# hot-wand.net
KiCad netlist of a schematic drawn in EAGLE
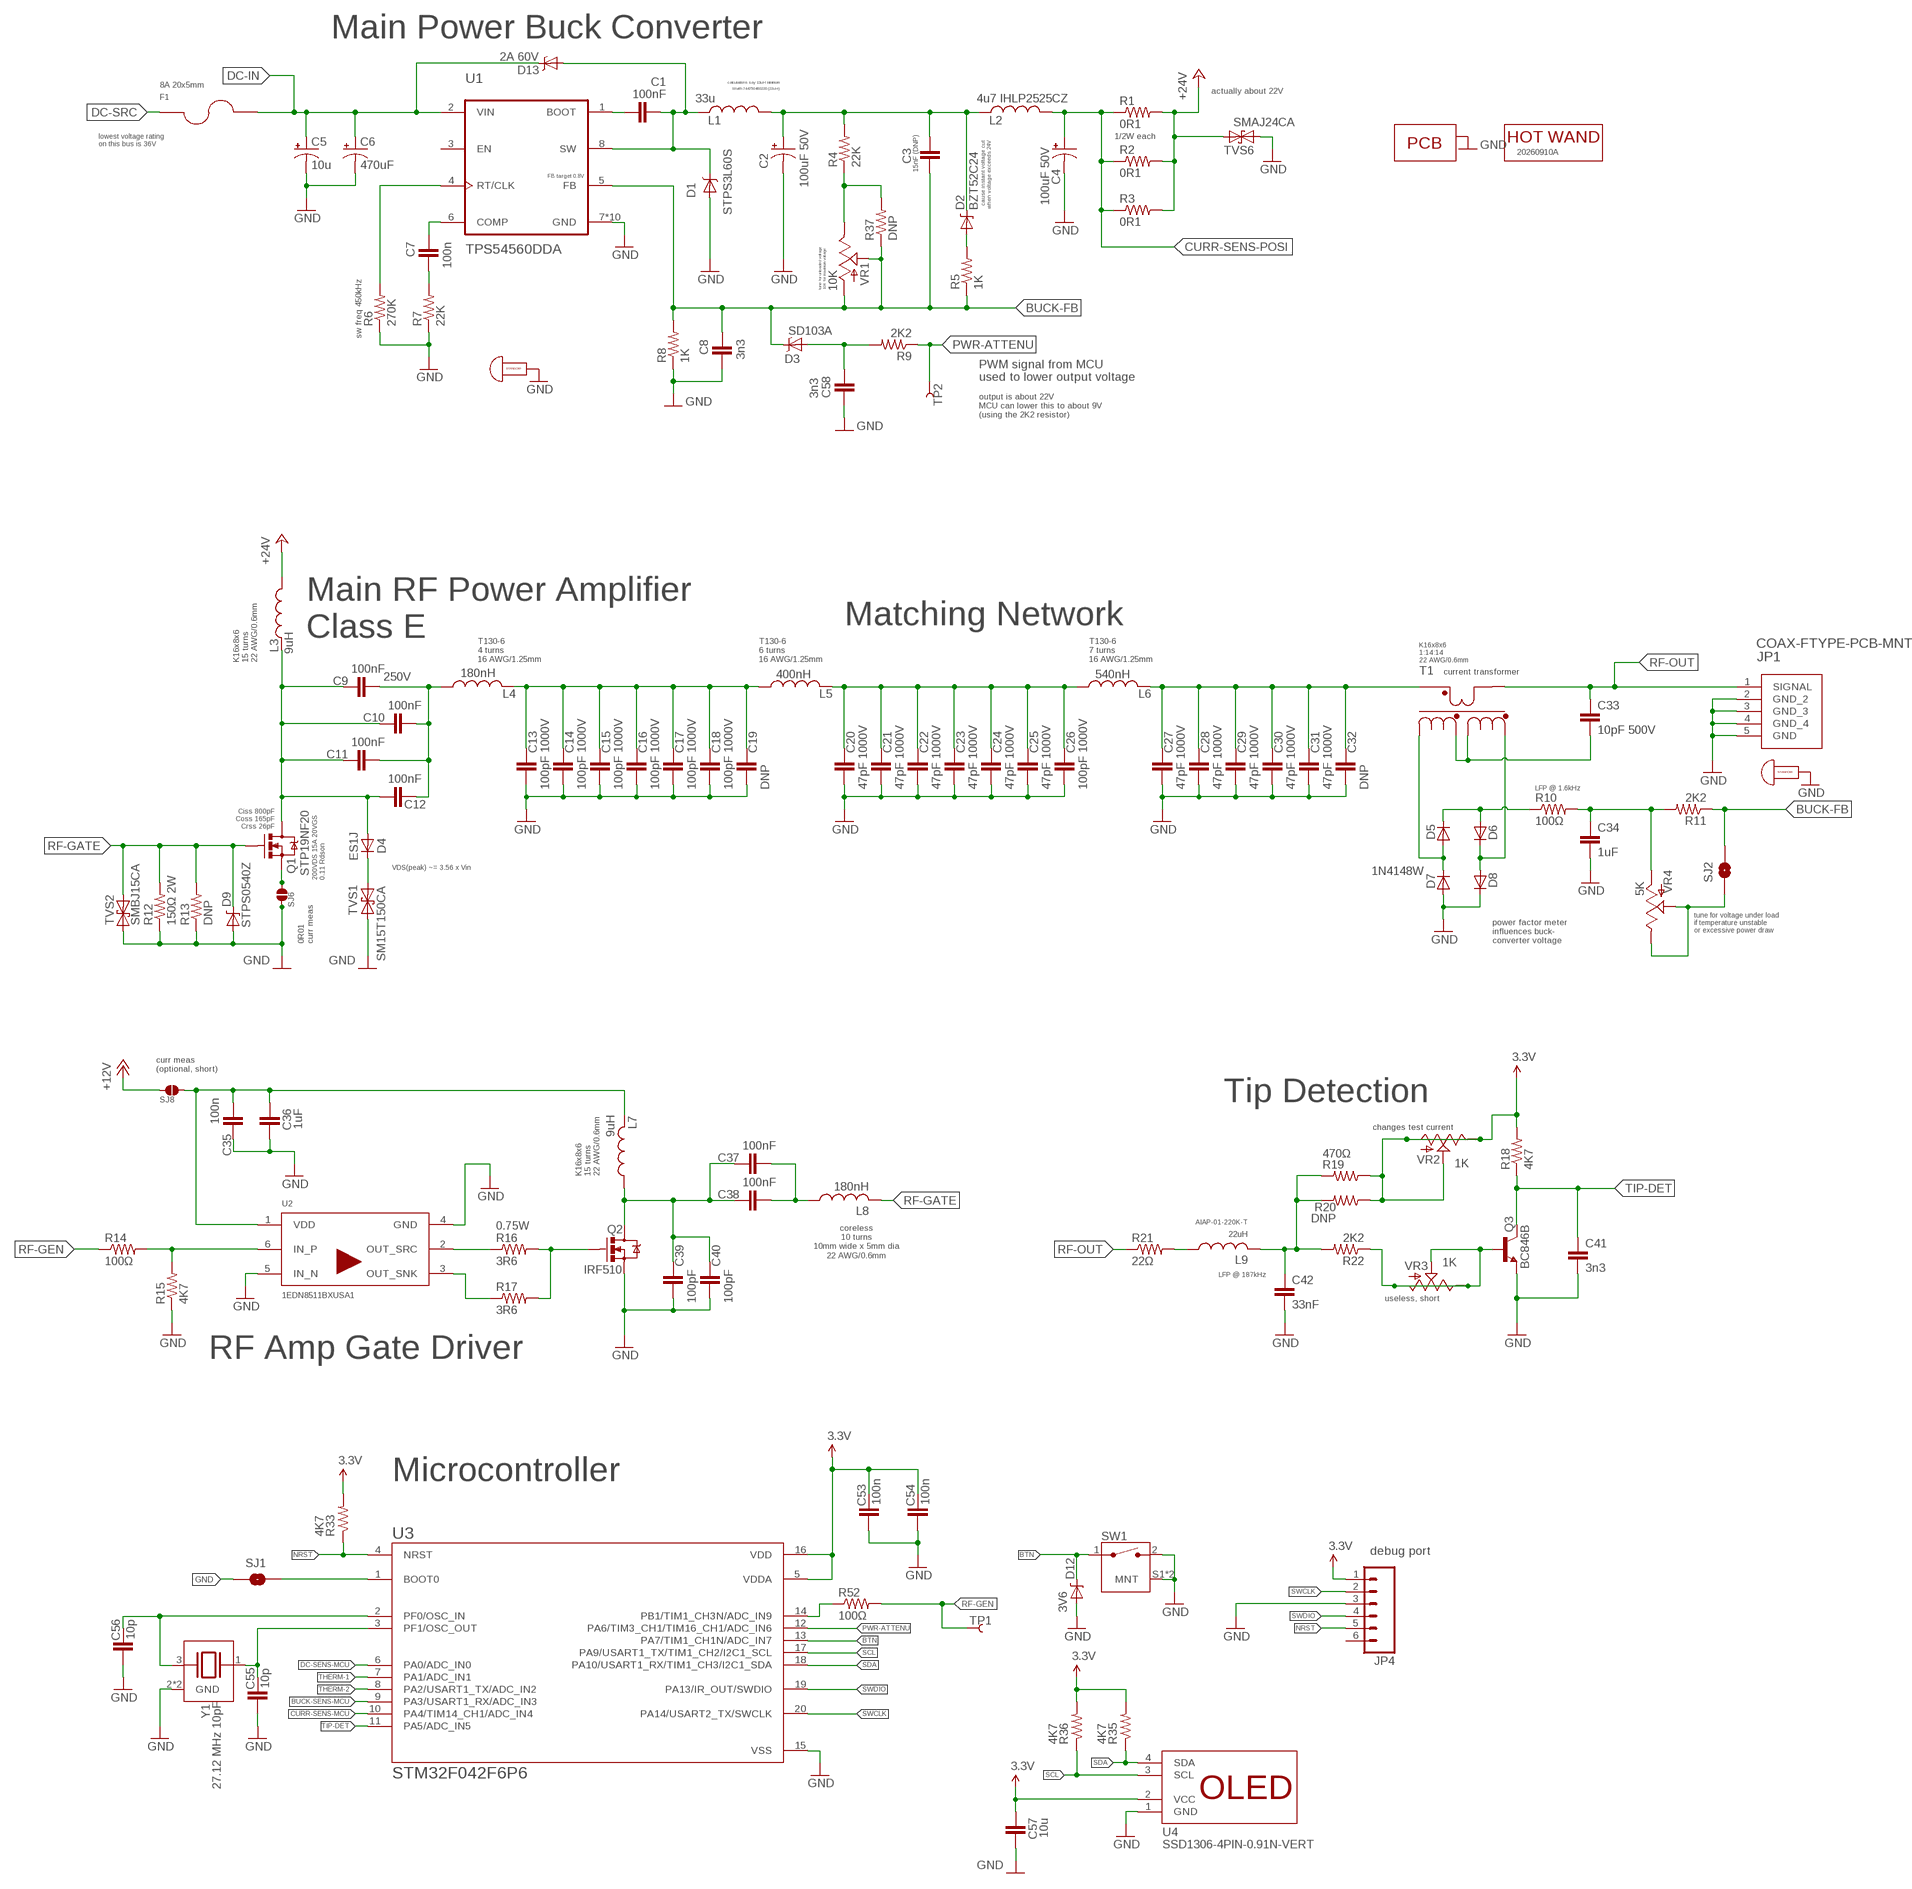
[diagram p0: schematic, sheet 1, part 1 of 2]
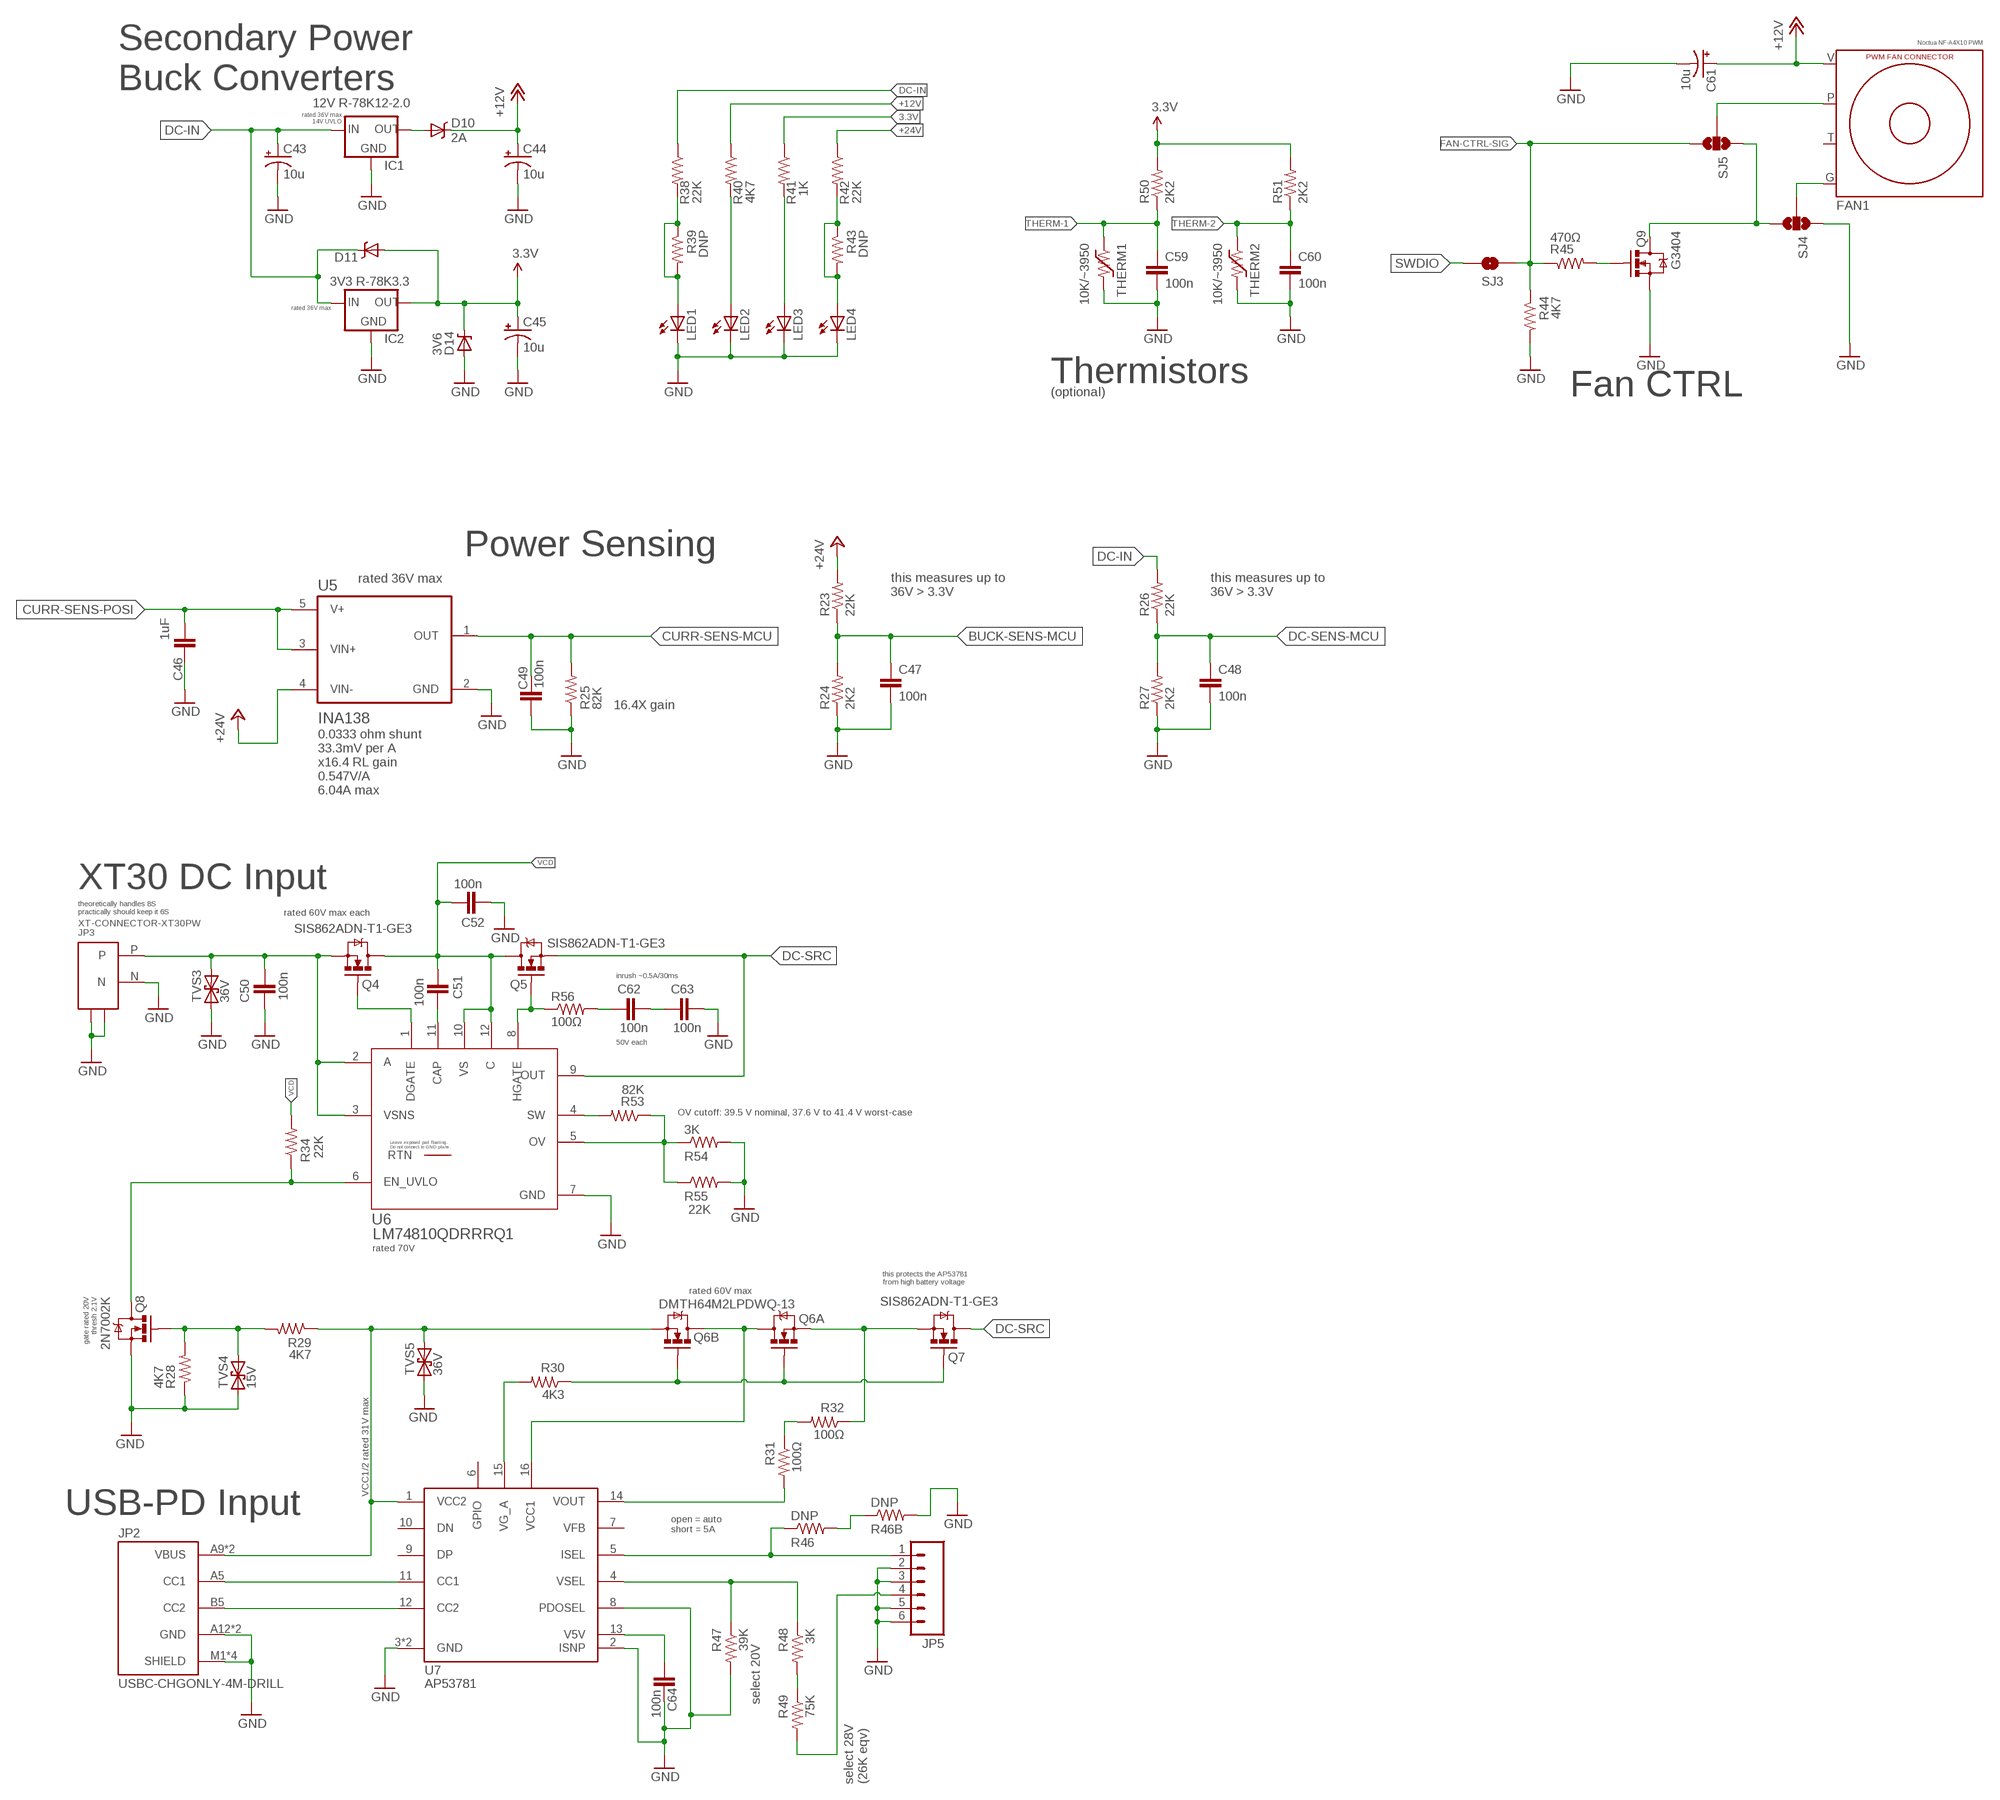
[diagram p1: schematic, sheet 1, part 2 of 2]

(export (version "E")
  (design (tool "Eeschema 10.0.6"))
  (components
    (comp (ref "C1")
      (value "100nF")
      (footprint "eagle-import:0603-CAP")
      (fields (field (name "JLCPARTNUM") "C14663"))
      (libsource (lib "eagle-import") (part "CAP0603-CAP"))
    )
    (comp (ref "C2")
      (value "100uF 50V")
      (footprint "eagle-import:CPOL-RADIAL-COMBO-10MM")
      (fields (field (name "JLC-DNP") "1") (field (name "PARTNUM") "EEU-FR1H101B;EEU-FR1J101B"))
      (libsource (lib "eagle-import") (part "CAP_POLPTH5"))
    )
    (comp (ref "C3")
      (value "15nF (DNP)")
      (footprint "eagle-import:0805")
      (libsource (lib "eagle-import") (part "CAP0805"))
    )
    (comp (ref "C4")
      (value "100uF 50V")
      (footprint "eagle-import:CPOL-RADIAL-COMBO-10MM")
      (fields (field (name "JLC-DNP") "1"))
      (libsource (lib "eagle-import") (part "CAP_POLPTH5"))
    )
    (comp (ref "C5")
      (value "10u")
      (footprint "eagle-import:EIA3216-KIT")
      (fields
        (field (name "JLCPARTNUM") "C13585")
        (field (name "PARTNUM") "MLASU31LBB5106KTNA01;GRT31CR61H106KE01K")
      )
      (libsource (lib "eagle-import") (part "CAP_POL1206-KIT"))
    )
    (comp (ref "C6")
      (value "470uF")
      (footprint "eagle-import:CPOL-RADIAL-1000UF-25V")
      (fields (field (name "JLC-DNP") "1") (field (name "PARTNUM") "UHW1H471MPD;EEU-FR1H471;EEU-FR1H471B"))
      (libsource (lib "eagle-import") (part "CAP_POLPTH4"))
    )
    (comp (ref "C7")
      (value "100n")
      (footprint "eagle-import:0603-CAP")
      (fields (field (name "JLCPARTNUM") "C14663"))
      (libsource (lib "eagle-import") (part "CAP0603-CAP"))
    )
    (comp (ref "C8")
      (value "3n3")
      (footprint "eagle-import:0603-CAP")
      (fields (field (name "JLCPARTNUM") "C1613"))
      (libsource (lib "eagle-import") (part "CAP0603-CAP"))
    )
    (comp (ref "C9")
      (value "100nF")
      (footprint "eagle-import:0805-L")
      (fields
        (field (name "JLCPARTNUM") "C5182461")
        (field (name "PARTNUM") "CHV0805N250104KXT;MBASQ21GAB7104KTCA01;MBASQ21GAB7104MTCA01")
      )
      (libsource (lib "eagle-import") (part "CAP0805-L"))
    )
    (comp (ref "C10")
      (value "100nF")
      (footprint "eagle-import:0805-L")
      (fields
        (field (name "JLCPARTNUM") "C5182461")
        (field (name "PARTNUM") "CHV0805N250104KXT;MBASQ21GAB7104KTCA01;MBASQ21GAB7104MTCA01")
      )
      (libsource (lib "eagle-import") (part "CAP0805-L"))
    )
    (comp (ref "C11")
      (value "100nF")
      (footprint "eagle-import:0805-L")
      (fields
        (field (name "JLCPARTNUM") "C5182461")
        (field (name "PARTNUM") "CHV0805N250104KXT;MBASQ21GAB7104KTCA01;MBASQ21GAB7104MTCA01")
      )
      (libsource (lib "eagle-import") (part "CAP0805-L"))
    )
    (comp (ref "C12")
      (value "100nF")
      (footprint "eagle-import:0805-L")
      (fields
        (field (name "JLCPARTNUM") "C5182461")
        (field (name "PARTNUM") "CHV0805N250104KXT;MBASQ21GAB7104KTCA01;MBASQ21GAB7104MTCA01")
      )
      (libsource (lib "eagle-import") (part "CAP0805-L"))
    )
    (comp (ref "C13")
      (value "100pF 1000V")
      (footprint "eagle-import:0805-L")
      (fields
        (field (name "JLCPARTNUM") "C6958299")
        (field (name "PARTNUM") "QCCT102Q101J1GV001E")
        (field (name "PLACEHOLDERPART") "C28233")
      )
      (libsource (lib "eagle-import") (part "CAP0805-L"))
    )
    (comp (ref "C14")
      (value "100pF 1000V")
      (footprint "eagle-import:0805-L")
      (fields (field (name "JLCPARTNUM") "C6958299"))
      (libsource (lib "eagle-import") (part "CAP0805-L"))
    )
    (comp (ref "C15")
      (value "100pF 1000V")
      (footprint "eagle-import:0805-L")
      (fields (field (name "JLCPARTNUM") "C6958299"))
      (libsource (lib "eagle-import") (part "CAP0805-L"))
    )
    (comp (ref "C16")
      (value "100pF 1000V")
      (footprint "eagle-import:0805-L")
      (fields (field (name "JLCPARTNUM") "C6958299"))
      (libsource (lib "eagle-import") (part "CAP0805-L"))
    )
    (comp (ref "C17")
      (value "100pF 1000V")
      (footprint "eagle-import:0805-L")
      (fields (field (name "JLCPARTNUM") "C6958299"))
      (libsource (lib "eagle-import") (part "CAP0805-L"))
    )
    (comp (ref "C18")
      (value "100pF 1000V")
      (footprint "eagle-import:0805-L")
      (fields (field (name "JLCPARTNUM") "C6958299"))
      (libsource (lib "eagle-import") (part "CAP0805-L"))
    )
    (comp (ref "C19")
      (value "DNP")
      (footprint "eagle-import:0805-L")
      (fields (field (name "JLCPARTNUM") "C6958299"))
      (libsource (lib "eagle-import") (part "CAP0805-L"))
    )
    (comp (ref "C20")
      (value "47pF 1000V")
      (footprint "eagle-import:0805-L")
      (fields (field (name "JLCPARTNUM") "C6366545") (field (name "PARTNUM") "QCCT102Q470J1GV001E"))
      (libsource (lib "eagle-import") (part "CAP0805-L"))
    )
    (comp (ref "C21")
      (value "47pF 1000V")
      (footprint "eagle-import:0805-L")
      (fields (field (name "JLCPARTNUM") "C6366545"))
      (libsource (lib "eagle-import") (part "CAP0805-L"))
    )
    (comp (ref "C22")
      (value "47pF 1000V")
      (footprint "eagle-import:0805-L")
      (fields (field (name "JLCPARTNUM") "C6366545"))
      (libsource (lib "eagle-import") (part "CAP0805-L"))
    )
    (comp (ref "C23")
      (value "47pF 1000V")
      (footprint "eagle-import:0805-L")
      (fields (field (name "JLCPARTNUM") "C6366545"))
      (libsource (lib "eagle-import") (part "CAP0805-L"))
    )
    (comp (ref "C24")
      (value "47pF 1000V")
      (footprint "eagle-import:0805-L")
      (fields (field (name "JLCPARTNUM") "C6366545"))
      (libsource (lib "eagle-import") (part "CAP0805-L"))
    )
    (comp (ref "C25")
      (value "47pF 1000V")
      (footprint "eagle-import:0805-L")
      (fields (field (name "JLCPARTNUM") "C6366545"))
      (libsource (lib "eagle-import") (part "CAP0805-L"))
    )
    (comp (ref "C26")
      (value "100pF 1000V")
      (footprint "eagle-import:0805-L")
      (fields (field (name "JLCPARTNUM") "C6958299"))
      (libsource (lib "eagle-import") (part "CAP0805-L"))
    )
    (comp (ref "C27")
      (value "47pF 1000V")
      (footprint "eagle-import:0805-L")
      (fields (field (name "JLCPARTNUM") "C6366545"))
      (libsource (lib "eagle-import") (part "CAP0805-L"))
    )
    (comp (ref "C28")
      (value "47pF 1000V")
      (footprint "eagle-import:0805-L")
      (fields (field (name "JLCPARTNUM") "C6366545"))
      (libsource (lib "eagle-import") (part "CAP0805-L"))
    )
    (comp (ref "C29")
      (value "47pF 1000V")
      (footprint "eagle-import:0805-L")
      (fields (field (name "JLCPARTNUM") "C6366545"))
      (libsource (lib "eagle-import") (part "CAP0805-L"))
    )
    (comp (ref "C30")
      (value "47pF 1000V")
      (footprint "eagle-import:0805-L")
      (fields (field (name "JLCPARTNUM") "C6366545"))
      (libsource (lib "eagle-import") (part "CAP0805-L"))
    )
    (comp (ref "C31")
      (value "47pF 1000V")
      (footprint "eagle-import:0805-L")
      (fields (field (name "JLCPARTNUM") "C6366545"))
      (libsource (lib "eagle-import") (part "CAP0805-L"))
    )
    (comp (ref "C32")
      (value "DNP")
      (footprint "eagle-import:0805-L")
      (fields (field (name "JLC-DNP") "1"))
      (libsource (lib "eagle-import") (part "CAP0805-L"))
    )
    (comp (ref "C33")
      (value "10pF 500V")
      (footprint "eagle-import:0805-L")
      (fields (field (name "JLCPARTNUM") "C6629873") (field (name "PARTNUM") "QCCT102Q100J1GV001E"))
      (libsource (lib "eagle-import") (part "CAP0805-L"))
    )
    (comp (ref "C34")
      (value "1uF")
      (footprint "eagle-import:0603-CAP")
      (fields (field (name "JLCPARTNUM") "C15849"))
      (libsource (lib "eagle-import") (part "CAP0603-CAP"))
    )
    (comp (ref "C35")
      (value "100n")
      (footprint "eagle-import:0603-CAP")
      (fields (field (name "JLCPARTNUM") "C14663"))
      (libsource (lib "eagle-import") (part "CAP0603-CAP"))
    )
    (comp (ref "C36")
      (value "1uF")
      (footprint "eagle-import:0603-CAP")
      (fields (field (name "JLCPARTNUM") "C15849"))
      (libsource (lib "eagle-import") (part "CAP0603-CAP"))
    )
    (comp (ref "C37")
      (value "100nF")
      (footprint "eagle-import:0805-L")
      (fields
        (field (name "JLCPARTNUM") "C5182461")
        (field (name "PARTNUM") "CHV0805N250104KXT;MBASQ21GAB7104KTCA01;MBASQ21GAB7104MTCA01")
      )
      (libsource (lib "eagle-import") (part "CAP0805-L"))
    )
    (comp (ref "C38")
      (value "100nF")
      (footprint "eagle-import:0805-L")
      (fields
        (field (name "JLCPARTNUM") "C5182461")
        (field (name "PARTNUM") "CHV0805N250104KXT;MBASQ21GAB7104KTCA01;MBASQ21GAB7104MTCA01")
      )
      (libsource (lib "eagle-import") (part "CAP0805-L"))
    )
    (comp (ref "C39")
      (value "100pF")
      (footprint "eagle-import:0805-L")
      (fields (field (name "JLCPARTNUM") "C6958299"))
      (libsource (lib "eagle-import") (part "CAP0805-L"))
    )
    (comp (ref "C40")
      (value "100pF")
      (footprint "eagle-import:0805-L")
      (fields (field (name "JLCPARTNUM") "C6958299"))
      (libsource (lib "eagle-import") (part "CAP0805-L"))
    )
    (comp (ref "C41")
      (value "3n3")
      (footprint "eagle-import:0603-CAP")
      (fields (field (name "JLCPARTNUM") "C1613"))
      (libsource (lib "eagle-import") (part "CAP0603-CAP"))
    )
    (comp (ref "C42")
      (value "33nF")
      (footprint "eagle-import:0603-CAP")
      (fields (field (name "JLCPARTNUM") "C21117"))
      (libsource (lib "eagle-import") (part "CAP0603-CAP"))
    )
    (comp (ref "C43")
      (value "10u")
      (footprint "eagle-import:EIA3216-KIT")
      (fields
        (field (name "JLCPARTNUM") "C13585")
        (field (name "PARTNUM") "MLASU31LBB5106KTNA01;GRT31CR61H106KE01K")
      )
      (libsource (lib "eagle-import") (part "CAP_POL1206-KIT"))
    )
    (comp (ref "C44")
      (value "10u")
      (footprint "eagle-import:EIA3216-KIT")
      (fields (field (name "JLCPARTNUM") "C13585") (field (name "PARTNUM") "TAJA106K016TNJ;T491A106K016AT"))
      (libsource (lib "eagle-import") (part "CAP_POL1206-KIT"))
    )
    (comp (ref "C45")
      (value "10u")
      (footprint "eagle-import:EIA3216")
      (fields (field (name "JLCPARTNUM") "C13585") (field (name "PARTNUM") "TAJA106K016TNJ;T491A106K016AT"))
      (libsource (lib "eagle-import") (part "CAP_POL1206"))
    )
    (comp (ref "C46")
      (value "1uF")
      (footprint "eagle-import:0603-CAP")
      (fields (field (name "JLCPARTNUM") "C15849"))
      (libsource (lib "eagle-import") (part "CAP0603-CAP"))
    )
    (comp (ref "C47")
      (value "100n")
      (footprint "eagle-import:0603-CAP")
      (libsource (lib "eagle-import") (part "CAP0603-CAP"))
    )
    (comp (ref "C48")
      (value "100n")
      (footprint "eagle-import:0603-CAP")
      (fields (field (name "JLCPARTNUM") "C14663"))
      (libsource (lib "eagle-import") (part "CAP0603-CAP"))
    )
    (comp (ref "C49")
      (value "100n")
      (footprint "eagle-import:0603-CAP")
      (fields (field (name "JLCPARTNUM") "C14663"))
      (libsource (lib "eagle-import") (part "CAP0603-CAP"))
    )
    (comp (ref "C50")
      (value "100n")
      (footprint "eagle-import:0603-CAP")
      (fields (field (name "JLCPARTNUM") "C14663"))
      (libsource (lib "eagle-import") (part "CAP0603-CAP"))
    )
    (comp (ref "C51")
      (value "100n")
      (footprint "eagle-import:0603-CAP")
      (fields (field (name "JLCPARTNUM") "C14663"))
      (libsource (lib "eagle-import") (part "CAP0603-CAP"))
    )
    (comp (ref "C52")
      (value "100n")
      (footprint "eagle-import:0603-CAP")
      (fields (field (name "JLCPARTNUM") "C14663"))
      (libsource (lib "eagle-import") (part "CAP0603-CAP"))
    )
    (comp (ref "C53")
      (value "100n")
      (footprint "eagle-import:0603-CAP")
      (fields (field (name "JLCPARTNUM") "C14663"))
      (libsource (lib "eagle-import") (part "CAP0603-CAP"))
    )
    (comp (ref "C54")
      (value "100n")
      (footprint "eagle-import:0603-CAP")
      (fields (field (name "JLCPARTNUM") "C14663"))
      (libsource (lib "eagle-import") (part "CAP0603-CAP"))
    )
    (comp (ref "C55")
      (value "10p")
      (footprint "eagle-import:0603-CAP")
      (fields (field (name "JLCPARTNUM") "C1634"))
      (libsource (lib "eagle-import") (part "CAP0603-CAP"))
    )
    (comp (ref "C56")
      (value "10p")
      (footprint "eagle-import:0603-CAP")
      (fields (field (name "JLCPARTNUM") "C1634"))
      (libsource (lib "eagle-import") (part "CAP0603-CAP"))
    )
    (comp (ref "C57")
      (value "10u")
      (footprint "eagle-import:1206")
      (fields (field (name "JLCPARTNUM") "C13585"))
      (libsource (lib "eagle-import") (part "CAP1206"))
    )
    (comp (ref "C58")
      (value "3n3")
      (footprint "eagle-import:0603-CAP")
      (fields (field (name "JLCPARTNUM") "C1613"))
      (libsource (lib "eagle-import") (part "CAP0603-CAP"))
    )
    (comp (ref "C59")
      (value "100n")
      (footprint "eagle-import:0603-CAP")
      (fields (field (name "JLCPARTNUM") "C14663"))
      (libsource (lib "eagle-import") (part "CAP0603-CAP"))
    )
    (comp (ref "C60")
      (value "100n")
      (footprint "eagle-import:0603-CAP")
      (fields (field (name "JLCPARTNUM") "C14663"))
      (libsource (lib "eagle-import") (part "CAP0603-CAP"))
    )
    (comp (ref "C61")
      (value "10u")
      (footprint "eagle-import:EIA3216-KIT")
      (fields
        (field (name "JLCPARTNUM") "C13585")
        (field (name "PARTNUM") "MLASU31LBB5106KTNA01;GRT31CR61H106KE01K")
      )
      (libsource (lib "eagle-import") (part "CAP_POL1206-KIT"))
    )
    (comp (ref "C62")
      (value "100n")
      (footprint "eagle-import:0603-CAP")
      (fields (field (name "JLCPARTNUM") "C14663"))
      (libsource (lib "eagle-import") (part "CAP0603-CAP"))
    )
    (comp (ref "C63")
      (value "100n")
      (footprint "eagle-import:0603-CAP")
      (fields (field (name "JLCPARTNUM") "C14663"))
      (libsource (lib "eagle-import") (part "CAP0603-CAP"))
    )
    (comp (ref "C64")
      (value "100n")
      (footprint "eagle-import:0603-CAP")
      (fields (field (name "JLCPARTNUM") "C14663"))
      (libsource (lib "eagle-import") (part "CAP0603-CAP"))
    )
    (comp (ref "D1")
      (value "STPS3L60S")
      (footprint "eagle-import:SMC")
      (fields (field (name "JLCPARTNUM") "C2971007"))
      (libsource (lib "eagle-import") (part "DIODE-SCHOTTKYSMC"))
    )
    (comp (ref "D2")
      (value "BZT52C24")
      (footprint "eagle-import:SOD123FL")
      (fields (field (name "JLCPARTNUM") "C2109"))
      (libsource (lib "eagle-import") (part "DIODE-ZENERSOD123FL"))
    )
    (comp (ref "D3")
      (value "SD103A")
      (footprint "eagle-import:SOD-323")
      (fields (field (name "JLCPARTNUM") "C7420360"))
      (libsource (lib "eagle-import") (part "DIODE-SCHOTTKYSOD-323"))
    )
    (comp (ref "D4")
      (value "ES1J")
      (footprint "eagle-import:SMA-DIODE")
      (fields (field (name "JLCPARTNUM") "C64879"))
      (libsource (lib "eagle-import") (part "DIODESMA"))
    )
    (comp (ref "D5")
      (value "4148")
      (footprint "eagle-import:SOD123FL")
      (fields (field (name "JLCPARTNUM") "C84367"))
      (libsource (lib "eagle-import") (part "DIODESOD123FL"))
    )
    (comp (ref "D6")
      (value "4148")
      (footprint "eagle-import:SOD123FL")
      (fields (field (name "JLCPARTNUM") "C84367"))
      (libsource (lib "eagle-import") (part "DIODESOD123FL"))
    )
    (comp (ref "D7")
      (value "1N4148W")
      (footprint "eagle-import:SOD123FL")
      (fields (field (name "JLCPARTNUM") "C84367"))
      (libsource (lib "eagle-import") (part "DIODESOD123FL"))
    )
    (comp (ref "D8")
      (value "4148")
      (footprint "eagle-import:SOD123FL")
      (fields (field (name "JLCPARTNUM") "C84367"))
      (libsource (lib "eagle-import") (part "DIODESOD123FL"))
    )
    (comp (ref "D9")
      (value "STPS0540Z")
      (footprint "eagle-import:SOD123FL")
      (fields (field (name "JLCPARTNUM") "C181835"))
      (libsource (lib "eagle-import") (part "DIODE-ZENERSOD123FL"))
    )
    (comp (ref "D10")
      (value "2A")
      (footprint "eagle-import:SMA-DIODE")
      (fields (field (name "JLCPARTNUM") "C698873") (field (name "PARTNUM") "VSSAF5N50;SL36A"))
      (libsource (lib "eagle-import") (part "DIODE-SCHOTTKY_"))
    )
    (comp (ref "D11")
      (value "DIODE-SCHOTTKY_")
      (footprint "eagle-import:SMA-DIODE")
      (fields (field (name "JLCPARTNUM") "C698873"))
      (libsource (lib "eagle-import") (part "DIODE-SCHOTTKY_"))
    )
    (comp (ref "D12")
      (value "3V6")
      (footprint "eagle-import:SOD-323")
      (fields
        (field (name "JLCPARTNUM") "C840638")
        (field (name "PARTNUM") "ESDLC3V3D3B-TP;CDSOD323-T03SC;SD03LCC")
      )
      (libsource (lib "eagle-import") (part "DIODE-ZENER-BZT52"))
    )
    (comp (ref "D13")
      (value "2A 60V")
      (footprint "eagle-import:SOD123FL")
      (fields (field (name "JLCPARTNUM") "C53340922") (field (name "PARTNUM") "STPS2L60ZFY"))
      (libsource (lib "eagle-import") (part "DIODE-SCHOTTKYSOD123FL"))
    )
    (comp (ref "D14")
      (value "3V6")
      (footprint "eagle-import:SOD-323")
      (fields
        (field (name "JLCPARTNUM") "C840638")
        (field (name "PARTNUM") "ESDLC3V3D3B-TP;CDSOD323-T03SC;SD03LCC")
      )
      (libsource (lib "eagle-import") (part "DIODE-ZENER-BZT52"))
    )
    (comp (ref "F1")
      (value "8A 20x5mm")
      (footprint "eagle-import:FUSE_5MM")
      (fields (field (name "JLC-DNP") "1") (field (name "PARTNUM") "Keystone 3518P"))
      (libsource (lib "eagle-import") (part "FUSEX20MM"))
    )
    (comp (ref "FAN1")
      (value "FAN-CONN-X4-CONN-X4")
      (footprint "eagle-import:FAN-CONN-X4")
      (libsource (lib "eagle-import") (part "FAN-CONN-X4-CONN-X4"))
    )
    (comp (ref "IC1")
      (value "12V R-78K12-2.0")
      (footprint "eagle-import:TO220-BUCK-12V")
      (fields (field (name "JLC-DNP") "1"))
      (libsource (lib "eagle-import") (part "V_REG_78XX-BUCK"))
    )
    (comp (ref "IC2")
      (value "3V3 R-78K3.3")
      (footprint "eagle-import:TO220-BUCK-3.3V")
      (fields (field (name "JLC-DNP") "1"))
      (libsource (lib "eagle-import") (part "V_REG_78XX-BUCK-3.3V"))
    )
    (comp (ref "JP1")
      (value "COAX-FTYPE-PCB-MNT")
      (footprint "eagle-import:CONN_73330-0030_MOL")
      (fields
        (field (name "DIGIKEY_PART_NUMBER") "WM5387-ND")
        (field (name "MF") "Molex")
        (field (name "MP") "733300030")
        (field (name "JLC-DNP") "1")
      )
      (libsource (lib "eagle-import") (part "COAX-FTYPE-PCB-MNT"))
    )
    (comp (ref "JP2")
      (value "USBC-CHGONLY-4M-DRILL")
      (footprint "eagle-import:SAMESKY_UJC-H-G-SMT-2-P6-TR-DRILL")
      (fields
        (field (name "DIGIKEY_PART_NUMBER") "2223-UJC-H-G-SMT-2-P6-TRCT-ND")
        (field (name "MF") "Same Sky")
        (field (name "MP") "UJC-H-G-SMT-2-P6-TR")
        (field (name "JLC-DNP") "1")
      )
      (libsource (lib "eagle-import") (part "USBC-CHGONLY-4M-DRILL"))
    )
    (comp (ref "JP3")
      (value "XT-CONNECTOR-XT30PW")
      (footprint "eagle-import:XT30PW")
      (fields (field (name "JLC-DNP") "1"))
      (libsource (lib "eagle-import") (part "XT-CONNECTOR-XT30PW"))
    )
    (comp (ref "JP4")
      (value "M06LOCK")
      (footprint "eagle-import:1X06_LOCK")
      (fields (field (name "JLC-DNP") "1"))
      (libsource (lib "eagle-import") (part "M06LOCK"))
    )
    (comp (ref "JP5")
      (value "M06LOCK")
      (footprint "eagle-import:1X06_LOCK")
      (libsource (lib "eagle-import") (part "M06LOCK"))
    )
    (comp (ref "L1")
      (value "33u")
      (footprint "eagle-import:IND_RADIAL_D12.7_COMBO")
      (fields (field (name "JLC-DNP") "1") (field (name "PARTNUM") "Wurth 744750460220 (22uH)"))
      (libsource (lib "eagle-import") (part "INDUCTORRADIAL_D12.7_COMBO"))
    )
    (comp (ref "L2")
      (value "4u7 IHLP2525CZ")
      (footprint "eagle-import:IND_IHLP-2525CZ_VIS-M")
      (fields (field (name "JLCPARTNUM") "C845027") (field (name "PARTNUM") "IHLP2525CZER4R7M11"))
      (libsource (lib "eagle-import") (part "INDUCTORIHLP-2525CZ_VIS-M"))
    )
    (comp (ref "L3")
      (value "9uH")
      (footprint "eagle-import:IND_K16X8X6_X2")
      (fields (field (name "JLC-DNP") "1"))
      (libsource (lib "eagle-import") (part "INDUCTOR-K16X8X6"))
    )
    (comp (ref "L4")
      (value "180nH")
      (footprint "eagle-import:IND_T130-6_X2")
      (fields (field (name "JLC-DNP") "1"))
      (libsource (lib "eagle-import") (part "INDUCTOR-T130-6"))
    )
    (comp (ref "L5")
      (value "400nH")
      (footprint "eagle-import:IND_T130-6_X2")
      (fields (field (name "JLC-DNP") "1"))
      (libsource (lib "eagle-import") (part "INDUCTOR-T130-6"))
    )
    (comp (ref "L6")
      (value "540nH")
      (footprint "eagle-import:IND_T130-6_X2")
      (fields (field (name "JLC-DNP") "1"))
      (libsource (lib "eagle-import") (part "INDUCTOR-T130-6"))
    )
    (comp (ref "L7")
      (value "9uH")
      (footprint "eagle-import:IND_K16X8X6_X2")
      (fields (field (name "JLC-DNP") "1"))
      (libsource (lib "eagle-import") (part "INDUCTOR-K16X8X6"))
    )
    (comp (ref "L8")
      (value "180nH")
      (footprint "eagle-import:IND-10X6MM")
      (fields (field (name "JLC-DNP") "1"))
      (libsource (lib "eagle-import") (part "L-USIND-10X6MM"))
    )
    (comp (ref "L9")
      (value "22uH")
      (footprint "eagle-import:TFI0410")
      (fields (field (name "JLC-DNP") "1") (field (name "PARTNUM") "AIAP-01-220K-T"))
      (libsource (lib "eagle-import") (part "L-USTFI0410"))
    )
    (comp (ref "LED1")
      (value "LED")
      (footprint "eagle-import:LED-0603")
      (fields (field (name "JLC-DNP") "1"))
      (libsource (lib "eagle-import") (part "LED0603"))
    )
    (comp (ref "LED2")
      (value "LED")
      (footprint "eagle-import:LED-0603")
      (fields (field (name "JLC-DNP") "1"))
      (libsource (lib "eagle-import") (part "LED0603"))
    )
    (comp (ref "LED3")
      (value "LED")
      (footprint "eagle-import:LED-0603")
      (fields (field (name "JLC-DNP") "1"))
      (libsource (lib "eagle-import") (part "LED0603"))
    )
    (comp (ref "LED4")
      (value "LED")
      (footprint "eagle-import:LED-0603")
      (fields (field (name "JLC-DNP") "1"))
      (libsource (lib "eagle-import") (part "LED0603"))
    )
    (comp (ref "PCB1")
      (value "PCB-OUTLINE")
      (footprint "eagle-import:PCB-OUTLINE")
      (fields (field (name "JLC-DNP") "1"))
      (libsource (lib "eagle-import") (part "PCB-OUTLINE"))
    )
    (comp (ref "PCB2")
      (value "PCB-ART-VERSION")
      (footprint "eagle-import:PCB-ART-VERSION")
      (fields (field (name "JLC-DNP") "1"))
      (libsource (lib "eagle-import") (part "PCB-ART-VERSION"))
    )
    (comp (ref "Q1")
      (value "STP19NF20")
      (footprint "eagle-import:TO220V-REAR")
      (fields (field (name "JLC-DNP") "1"))
      (libsource (lib "eagle-import") (part "MOSFET-NCHANNEL-TO220V-REAR"))
    )
    (comp (ref "Q2")
      (value "IRF510")
      (footprint "eagle-import:TO220V-REAR")
      (fields (field (name "JLC-DNP") "1"))
      (libsource (lib "eagle-import") (part "MOSFET-NCHANNEL-TO220V-REAR"))
    )
    (comp (ref "Q3")
      (value "BC846B")
      (footprint "eagle-import:SOT23-3")
      (fields (field (name "JLCPARTNUM") "C181138"))
      (libsource (lib "eagle-import") (part "TRANSISTOR_NPNSOT23-3"))
    )
    (comp (ref "Q4")
      (value "SIS862ADN-T1-GE3")
      (footprint "eagle-import:POWERPAK-1212-8")
      (libsource (lib "eagle-import") (part "MOSFET-NCHANNEL-POWERPAK1212-8"))
    )
    (comp (ref "Q5")
      (value "SIS862ADN-T1-GE3")
      (footprint "eagle-import:POWERPAK-1212-8")
      (libsource (lib "eagle-import") (part "MOSFET-NCHANNEL-POWERPAK1212-8"))
    )
    (comp (ref "Q6")
      (value "DMTH64M2LPDWQ-13")
      (footprint "eagle-import:POWERPAK-SO8-X2")
      (fields (field (name "JLC-DNP") "1"))
      (libsource (lib "eagle-import") (part "MOSFET-NCHAN-X2-PPSO8X2"))
    )
    (comp (ref "Q7")
      (value "SIS862ADN-T1-GE3")
      (footprint "eagle-import:POWERPAK-1212-8")
      (libsource (lib "eagle-import") (part "MOSFET-NCHANNEL-POWERPAK1212-8"))
    )
    (comp (ref "Q8")
      (value "2N7002K")
      (footprint "eagle-import:SOT23-3")
      (fields
        (field (name "JLCPARTNUM") "C14498;C547263;C5224211;C54347659")
        (field (name "PARTNUM") "2N7002K;SSM3K388R,LF;Si2318CDS-T1-GE3;PMV60ENEAR")
      )
      (libsource (lib "eagle-import") (part "MOSFET-NCHANNELSMD"))
    )
    (comp (ref "Q9")
      (value "G3404")
      (footprint "eagle-import:SOT23-3")
      (fields
        (field (name "JLCPARTNUM") "C14498;C547263;C96615")
        (field (name "PARTNUM") "G3404;MMFTN3404A;PJA3404A;Si2318CDS-T1-GE3;PMV60ENEAR")
      )
      (libsource (lib "eagle-import") (part "MOSFET-NCHANNELSMD"))
    )
    (comp (ref "R1")
      (value "0R1")
      (footprint "eagle-import:1206")
      (fields (field (name "JLCPARTNUM") "C188071") (field (name "PARTNUM") "KDV12DR100ET;VMK-R033-1.0-U"))
      (libsource (lib "eagle-import") (part "RESISTOR1206"))
    )
    (comp (ref "R2")
      (value "0R1")
      (footprint "eagle-import:1206")
      (fields (field (name "JLCPARTNUM") "C188071") (field (name "PARTNUM") "KDV12DR100ET;VMK-R033-1.0-U"))
      (libsource (lib "eagle-import") (part "RESISTOR1206"))
    )
    (comp (ref "R3")
      (value "0R1")
      (footprint "eagle-import:1206")
      (fields (field (name "JLCPARTNUM") "C188071") (field (name "PARTNUM") "KDV12DR100ET;VMK-R033-1.0-U"))
      (libsource (lib "eagle-import") (part "RESISTOR1206"))
    )
    (comp (ref "R4")
      (value "22K")
      (footprint "eagle-import:0603-RES")
      (fields (field (name "JLCPARTNUM") "C31850"))
      (libsource (lib "eagle-import") (part "RESISTOR0603-RES"))
    )
    (comp (ref "R5")
      (value "1K")
      (footprint "eagle-import:0603-RES")
      (fields (field (name "JLCPARTNUM") "C21190"))
      (libsource (lib "eagle-import") (part "RESISTOR0603-RES"))
    )
    (comp (ref "R6")
      (value "270K")
      (footprint "eagle-import:0603-RES")
      (fields (field (name "JLCPARTNUM") "C137755"))
      (libsource (lib "eagle-import") (part "RESISTOR0603-RES"))
    )
    (comp (ref "R7")
      (value "22K")
      (footprint "eagle-import:0603-RES")
      (fields (field (name "JLCPARTNUM") "C31850"))
      (libsource (lib "eagle-import") (part "RESISTOR0603-RES"))
    )
    (comp (ref "R8")
      (value "1K")
      (footprint "eagle-import:0603-RES")
      (fields (field (name "JLCPARTNUM") "C21190"))
      (libsource (lib "eagle-import") (part "RESISTOR0603-RES"))
    )
    (comp (ref "R9")
      (value "2K2")
      (footprint "eagle-import:0603-RES")
      (fields (field (name "JLCPARTNUM") "C4190"))
      (libsource (lib "eagle-import") (part "RESISTOR0603-RES"))
    )
    (comp (ref "R10")
      (value "100Ω")
      (footprint "eagle-import:0603-RES")
      (fields (field (name "JLCPARTNUM") "C22775"))
      (libsource (lib "eagle-import") (part "RESISTOR0603-RES"))
    )
    (comp (ref "R11")
      (value "2K2")
      (footprint "eagle-import:0603-RES")
      (fields (field (name "JLCPARTNUM") "C4190"))
      (libsource (lib "eagle-import") (part "RESISTOR0603-RES"))
    )
    (comp (ref "R12")
      (value "150Ω 2W")
      (footprint "eagle-import:R2512")
      (fields (field (name "JLCPARTNUM") "C175287") (field (name "PARTNUM") "CRGP2512F150R"))
      (libsource (lib "eagle-import") (part "R-US_R2512"))
    )
    (comp (ref "R13")
      (value "DNP")
      (footprint "eagle-import:R2512")
      (fields (field (name "JLC-DNP") "1") (field (name "PARTNUM") "CRGP2512F150R"))
      (libsource (lib "eagle-import") (part "R-US_R2512"))
    )
    (comp (ref "R14")
      (value "100Ω")
      (footprint "eagle-import:0603-RES")
      (fields (field (name "JLCPARTNUM") "C22775"))
      (libsource (lib "eagle-import") (part "RESISTOR0603-RES"))
    )
    (comp (ref "R15")
      (value "4K7")
      (footprint "eagle-import:0603-RES")
      (fields (field (name "JLCPARTNUM") "C23162"))
      (libsource (lib "eagle-import") (part "RESISTOR0603-RES"))
    )
    (comp (ref "R16")
      (value "3R6")
      (footprint "eagle-import:1206")
      (fields (field (name "JLCPARTNUM") "C6301221"))
      (libsource (lib "eagle-import") (part "RESISTOR1206"))
    )
    (comp (ref "R17")
      (value "3R6")
      (footprint "eagle-import:1206")
      (fields (field (name "JLCPARTNUM") "C6301221"))
      (libsource (lib "eagle-import") (part "RESISTOR1206"))
    )
    (comp (ref "R18")
      (value "4K7")
      (footprint "eagle-import:0603-RES")
      (fields (field (name "JLCPARTNUM") "C23162"))
      (libsource (lib "eagle-import") (part "RESISTOR0603-RES"))
    )
    (comp (ref "R19")
      (value "470Ω")
      (footprint "eagle-import:0603-RES")
      (fields (field (name "JLCPARTNUM") "C23179"))
      (libsource (lib "eagle-import") (part "RESISTOR0603-RES"))
    )
    (comp (ref "R20")
      (value "DNP")
      (footprint "eagle-import:0805")
      (fields (field (name "JLC-DNP") "1"))
      (libsource (lib "eagle-import") (part "RESISTOR0805-RES"))
    )
    (comp (ref "R21")
      (value "22Ω")
      (footprint "eagle-import:R2512")
      (fields (field (name "JLCPARTNUM") "C5204054"))
      (libsource (lib "eagle-import") (part "RESISTOR2512"))
    )
    (comp (ref "R22")
      (value "2K2")
      (footprint "eagle-import:0603-RES")
      (fields (field (name "JLCPARTNUM") "C4190"))
      (libsource (lib "eagle-import") (part "RESISTOR0603-RES"))
    )
    (comp (ref "R23")
      (value "22K")
      (footprint "eagle-import:0603-RES")
      (fields (field (name "JLCPARTNUM") "C31850"))
      (libsource (lib "eagle-import") (part "RESISTOR0603-RES"))
    )
    (comp (ref "R24")
      (value "2K2")
      (footprint "eagle-import:0603-RES")
      (fields (field (name "JLCPARTNUM") "C4190"))
      (libsource (lib "eagle-import") (part "RESISTOR0603-RES"))
    )
    (comp (ref "R25")
      (value "82K")
      (footprint "eagle-import:0603-RES")
      (fields (field (name "JLCPARTNUM") "C23254"))
      (libsource (lib "eagle-import") (part "RESISTOR0603-RES"))
    )
    (comp (ref "R26")
      (value "22K")
      (footprint "eagle-import:0603-RES")
      (fields (field (name "JLCPARTNUM") "C31850"))
      (libsource (lib "eagle-import") (part "RESISTOR0603-RES"))
    )
    (comp (ref "R27")
      (value "2K2")
      (footprint "eagle-import:0603-RES")
      (fields (field (name "JLCPARTNUM") "C4190"))
      (libsource (lib "eagle-import") (part "RESISTOR0603-RES"))
    )
    (comp (ref "R28")
      (value "4K7")
      (footprint "eagle-import:0603-RES")
      (fields (field (name "JLCPARTNUM") "C23162"))
      (libsource (lib "eagle-import") (part "RESISTOR0603-RES"))
    )
    (comp (ref "R29")
      (value "4K7")
      (footprint "eagle-import:0603-RES")
      (fields (field (name "JLCPARTNUM") "C23162"))
      (libsource (lib "eagle-import") (part "RESISTOR0603-RES"))
    )
    (comp (ref "R30")
      (value "4K3")
      (footprint "eagle-import:0603-RES")
      (fields (field (name "JLCPARTNUM") "C23159"))
      (libsource (lib "eagle-import") (part "RESISTOR0603-RES"))
    )
    (comp (ref "R31")
      (value "100Ω")
      (footprint "eagle-import:0805")
      (fields (field (name "JLCPARTNUM") "C441975"))
      (libsource (lib "eagle-import") (part "RESISTOR0805-RES"))
    )
    (comp (ref "R32")
      (value "100Ω")
      (footprint "eagle-import:0805")
      (fields (field (name "JLCPARTNUM") "C441975"))
      (libsource (lib "eagle-import") (part "RESISTOR0805-RES"))
    )
    (comp (ref "R33")
      (value "4K7")
      (footprint "eagle-import:0603-RES")
      (fields (field (name "JLCPARTNUM") "C23162"))
      (libsource (lib "eagle-import") (part "RESISTOR0603-RES"))
    )
    (comp (ref "R34")
      (value "22K")
      (footprint "eagle-import:0603-RES")
      (fields (field (name "JLCPARTNUM") "C31850"))
      (libsource (lib "eagle-import") (part "RESISTOR0603-RES"))
    )
    (comp (ref "R35")
      (value "4K7")
      (footprint "eagle-import:0603-RES")
      (fields (field (name "JLCPARTNUM") "C23162"))
      (libsource (lib "eagle-import") (part "RESISTOR0603-RES"))
    )
    (comp (ref "R36")
      (value "4K7")
      (footprint "eagle-import:0603-RES")
      (fields (field (name "JLCPARTNUM") "C23162"))
      (libsource (lib "eagle-import") (part "RESISTOR0603-RES"))
    )
    (comp (ref "R37")
      (value "DNP")
      (footprint "eagle-import:0603-RES")
      (fields (field (name "JLC-DNP") "1"))
      (libsource (lib "eagle-import") (part "RESISTOR0603-RES"))
    )
    (comp (ref "R38")
      (value "22K")
      (footprint "eagle-import:0603-RES")
      (fields (field (name "JLCPARTNUM") "C31850"))
      (libsource (lib "eagle-import") (part "RESISTOR0603-RES"))
    )
    (comp (ref "R39")
      (value "DNP")
      (footprint "eagle-import:0603-RES")
      (fields (field (name "DNP") "1"))
      (libsource (lib "eagle-import") (part "RESISTOR0603-RES"))
    )
    (comp (ref "R40")
      (value "4K7")
      (footprint "eagle-import:0603-RES")
      (fields (field (name "JLCPARTNUM") "C23162"))
      (libsource (lib "eagle-import") (part "RESISTOR0603-RES"))
    )
    (comp (ref "R41")
      (value "1K")
      (footprint "eagle-import:0603-RES")
      (fields (field (name "JLCPARTNUM") "C21190"))
      (libsource (lib "eagle-import") (part "RESISTOR0603-RES"))
    )
    (comp (ref "R42")
      (value "22K")
      (footprint "eagle-import:0603-RES")
      (fields (field (name "JLCPARTNUM") "C31850"))
      (libsource (lib "eagle-import") (part "RESISTOR0603-RES"))
    )
    (comp (ref "R43")
      (value "DNP")
      (footprint "eagle-import:0603-RES")
      (fields (field (name "DNP") "1"))
      (libsource (lib "eagle-import") (part "RESISTOR0603-RES"))
    )
    (comp (ref "R44")
      (value "4K7")
      (footprint "eagle-import:0603-RES")
      (fields (field (name "JLCPARTNUM") "C23162"))
      (libsource (lib "eagle-import") (part "RESISTOR0603-RES"))
    )
    (comp (ref "R45")
      (value "470Ω")
      (footprint "eagle-import:0603-RES")
      (fields (field (name "JLCPARTNUM") "C23179"))
      (libsource (lib "eagle-import") (part "RESISTOR0603-RES"))
    )
    (comp (ref "R46")
      (value "DNP")
      (footprint "eagle-import:0603-RES")
      (fields (field (name "JLC-DNP") "1"))
      (libsource (lib "eagle-import") (part "RESISTOR0603-RES"))
    )
    (comp (ref "R46B")
      (value "DNP")
      (footprint "eagle-import:0603-RES")
      (fields (field (name "JLC-DNP") "1"))
      (libsource (lib "eagle-import") (part "RESISTOR0603-RES"))
    )
    (comp (ref "R47")
      (value "39K")
      (footprint "eagle-import:0603-RES")
      (fields (field (name "JLCPARTNUM") "C23153"))
      (libsource (lib "eagle-import") (part "RESISTOR0603-RES"))
    )
    (comp (ref "R48")
      (value "3K")
      (footprint "eagle-import:0603-RES")
      (fields (field (name "JLCPARTNUM") "C4211"))
      (libsource (lib "eagle-import") (part "RESISTOR0603-RES"))
    )
    (comp (ref "R49")
      (value "75K")
      (footprint "eagle-import:0603-RES")
      (fields (field (name "JLCPARTNUM") "C23242"))
      (libsource (lib "eagle-import") (part "RESISTOR0603-RES"))
    )
    (comp (ref "R50")
      (value "2K2")
      (footprint "eagle-import:0603-RES")
      (fields (field (name "JLCPARTNUM") "C4190"))
      (libsource (lib "eagle-import") (part "RESISTOR0603-RES"))
    )
    (comp (ref "R51")
      (value "2K2")
      (footprint "eagle-import:0603-RES")
      (fields (field (name "JLCPARTNUM") "C4190"))
      (libsource (lib "eagle-import") (part "RESISTOR0603-RES"))
    )
    (comp (ref "R52")
      (value "100Ω")
      (footprint "eagle-import:0603-RES")
      (fields (field (name "JLCPARTNUM") "C22775"))
      (libsource (lib "eagle-import") (part "RESISTOR0603-RES"))
    )
    (comp (ref "R53")
      (value "82K")
      (footprint "eagle-import:0603-RES")
      (fields (field (name "JLCPARTNUM") "C23254"))
      (libsource (lib "eagle-import") (part "RESISTOR0603-RES"))
    )
    (comp (ref "R54")
      (value "3K")
      (footprint "eagle-import:0603-RES")
      (fields (field (name "JLCPARTNUM") "C4211"))
      (libsource (lib "eagle-import") (part "RESISTOR0603-RES"))
    )
    (comp (ref "R55")
      (value "22K")
      (footprint "eagle-import:0603-RES")
      (fields (field (name "JLCPARTNUM") "C31850"))
      (libsource (lib "eagle-import") (part "RESISTOR0603-RES"))
    )
    (comp (ref "R56")
      (value "100Ω")
      (footprint "eagle-import:0805")
      (fields (field (name "JLCPARTNUM") "C441975"))
      (libsource (lib "eagle-import") (part "RESISTOR0805-RES"))
    )
    (comp (ref "SJ1")
      (value "SOLDERJUMPERNO")
      (footprint "eagle-import:SJ_2S-NO")
      (fields (field (name "JLC-DNP") "1"))
      (libsource (lib "eagle-import") (part "SOLDERJUMPERNO"))
    )
    (comp (ref "SJ2")
      (value "SOLDERJUMPERNO")
      (footprint "eagle-import:SJ_2S-NO")
      (fields (field (name "JLC-DNP") "1"))
      (libsource (lib "eagle-import") (part "SOLDERJUMPERNO"))
    )
    (comp (ref "SJ3")
      (value "SOLDERJUMPERNO")
      (footprint "eagle-import:SJ_2S-NO")
      (fields (field (name "JLC-DNP") "1"))
      (libsource (lib "eagle-import") (part "SOLDERJUMPERNO"))
    )
    (comp (ref "SJ4")
      (value "SOLDERJUMPER_2WAYS")
      (footprint "eagle-import:SJ_3")
      (libsource (lib "eagle-import") (part "SOLDERJUMPER_2WAYS"))
    )
    (comp (ref "SJ5")
      (value "SOLDERJUMPER_2WAYS")
      (footprint "eagle-import:SJ_3")
      (libsource (lib "eagle-import") (part "SOLDERJUMPER_2WAYS"))
    )
    (comp (ref "SJ6")
      (value "SJ-SMALL-1206-SJ")
      (footprint "eagle-import:1206-SJ")
      (libsource (lib "eagle-import") (part "SJ-SMALL-1206-SJ"))
    )
    (comp (ref "SJ7")
      (value "SJ-SMALL-1206-SJ")
      (footprint "eagle-import:1206-SJ")
      (libsource (lib "eagle-import") (part "SJ-SMALL-1206-SJ"))
    )
    (comp (ref "SJ8")
      (value "SJ-SMALL-1206-SJ")
      (footprint "eagle-import:1206-SJ")
      (libsource (lib "eagle-import") (part "SJ-SMALL-1206-SJ"))
    )
    (comp (ref "STANDOFF1")
      (value "STANDOFF-M2.5-4.5MMHEX")
      (footprint "eagle-import:STANDOFF-M2.5-4.5MMHEX")
      (libsource (lib "eagle-import") (part "STANDOFF-M2.5-4.5MMHEX"))
    )
    (comp (ref "STANDOFF2")
      (value "STANDOFF-M2.5-4.5MMHEX")
      (footprint "eagle-import:STANDOFF-M2.5-4.5MMHEX")
      (libsource (lib "eagle-import") (part "STANDOFF-M2.5-4.5MMHEX"))
    )
    (comp (ref "SW1")
      (value "SW-TACT-SIDE")
      (footprint "eagle-import:SW_1-1825027-1")
      (fields
        (field (name "COMMENT") "1-1825027-1")
        (field (name "DIGIKEY_PART_NUMBER") "450-1658-ND")
        (field (name "MF") "TE Connectivity")
        (field (name "JLC-DNP") "1")
        (field (name "PARTNUM") "MJTP1236D;TL1105JAF160R1RBLK")
      )
      (libsource (lib "eagle-import") (part "SW-TACT-SIDE"))
    )
    (comp (ref "T1")
      (value "XFORMER-1:14:14")
      (footprint "eagle-import:XFORMER-K16X8X6-1_14_14")
      (fields (field (name "JLC-DNP") "1"))
      (libsource (lib "eagle-import") (part "XFORMER-1{colon}14{colon}14"))
    )
    (comp (ref "THERM1")
      (value "10K/~3950")
      (footprint "eagle-import:1X02-2MM")
      (fields (field (name "JLC-DNP") "1") (field (name "PARTNUM") "B57891M0103K000"))
      (libsource (lib "eagle-import") (part "THERMISTOR-NTC-TH-2MM"))
    )
    (comp (ref "THERM2")
      (value "10K/~3950")
      (footprint "eagle-import:1X02-2MM")
      (fields (field (name "JLC-DNP") "1") (field (name "PARTNUM") "B57891M0103K000"))
      (libsource (lib "eagle-import") (part "THERMISTOR-NTC-TH-2MM"))
    )
    (comp (ref "TP1")
      (value "TEST-POINT-SQ-2MM")
      (footprint "eagle-import:PAD-SQ-2MM")
      (libsource (lib "eagle-import") (part "TEST-POINT-SQ-2MM"))
    )
    (comp (ref "TP2")
      (value "TEST-POINT-SQ-2MM")
      (footprint "eagle-import:PAD-SQ-2MM")
      (libsource (lib "eagle-import") (part "TEST-POINT-SQ-2MM"))
    )
    (comp (ref "TVS1")
      (value "SM15T150CA")
      (footprint "eagle-import:SMC")
      (fields (field (name "JLCPARTNUM") "C133715"))
      (libsource (lib "eagle-import") (part "TVSSMC"))
    )
    (comp (ref "TVS2")
      (value "SMBJ15CA")
      (footprint "eagle-import:SMA-DIODE")
      (fields (field (name "JLCPARTNUM") "C78809"))
      (libsource (lib "eagle-import") (part "TVS"))
    )
    (comp (ref "TVS3")
      (value "36V")
      (footprint "eagle-import:SMA")
      (fields (field (name "JLCPARTNUM") "C134984") (field (name "PARTNUM") "SMAJ36CA"))
      (libsource (lib "eagle-import") (part "TVSSMA"))
    )
    (comp (ref "TVS4")
      (value "15V")
      (footprint "eagle-import:SOD-323")
      (fields
        (field (name "JLCPARTNUM") "C2987151")
        (field (name "PARTNUM") "SD15C-01FTG;CDSOD323-T15SC;TSD15CDYFR")
      )
      (libsource (lib "eagle-import") (part "TVSSOD-323"))
    )
    (comp (ref "TVS5")
      (value "36V")
      (footprint "eagle-import:SMA")
      (fields (field (name "JLCPARTNUM") "C134984") (field (name "PARTNUM") "SMAJ36CA"))
      (libsource (lib "eagle-import") (part "TVSSMA"))
    )
    (comp (ref "TVS6")
      (value "SMAJ24CA")
      (footprint "eagle-import:SMA")
      (fields (field (name "JLCPARTNUM") "C148223"))
      (libsource (lib "eagle-import") (part "TVSSMA"))
    )
    (comp (ref "U1")
      (value "TPS54560DDA")
      (footprint "eagle-import:VREG_LM5017MR_NOPB")
      (fields (field (name "MF") "Texas Instruments") (field (name "JLCPARTNUM") "C31966"))
      (libsource (lib "eagle-import") (part "TPS54560DDA"))
    )
    (comp (ref "U2")
      (value "1EDN8511BXUSA1")
      (footprint "eagle-import:SOT95P280X145-6N-7-V")
      (fields (field (name "JLCPARTNUM") "C3655509"))
      (libsource (lib "eagle-import") (part "1EDN8511B"))
    )
    (comp (ref "U3")
      (value "STM32F042F6P6")
      (footprint "eagle-import:SOP65P640X120-20N")
      (fields (field (name "JLCPARTNUM") "C2969989"))
      (libsource (lib "eagle-import") (part "STM32F030F4P6"))
    )
    (comp (ref "U4")
      (value "SSD1306-4PIN-0.91N-VERT")
      (footprint "eagle-import:OLED-0.91IN-VERT")
      (fields (field (name "JLC-DNP") "1"))
      (libsource (lib "eagle-import") (part "OLED-SSD1306-4PIN-0.91N-VERT"))
    )
    (comp (ref "U5")
      (value "INA138")
      (footprint "eagle-import:SOT95P280X145-5N")
      (fields
        (field (name "MF") "Texas Instruments")
        (field (name "MP") "INA138NA/3K")
        (field (name "JLCPARTNUM") "C47914")
      )
      (libsource (lib "eagle-import") (part "INA138NA/3K"))
    )
    (comp (ref "U6")
      (value "LM74810QDRRRQ1")
      (footprint "eagle-import:DRR0012E-MFG")
      (fields
        (field (name "JLCPARTNUM") "C3215601")
        (field (name "COPYRIGHT") "Copyright (C) 2026 Ultra Librarian. All rights reserved.")
      )
      (libsource (lib "eagle-import") (part "LM74810QDRRRQ1"))
    )
    (comp (ref "U7")
      (value "AP53781")
      (footprint "eagle-import:QFN3030-16")
      (fields (field (name "JLCPARTNUM") "C52730979"))
      (libsource (lib "eagle-import") (part "AP53781-QFN3030-16"))
    )
    (comp (ref "VR1")
      (value "10K")
      (footprint "eagle-import:TRIM_35WR1KLFTR_V2")
      (fields (field (name "JLC-DNP") "1") (field (name "PARTNUM") "TC33X-2-103E"))
      (libsource (lib "eagle-import") (part "POT-35WR1KLFTR_V2"))
    )
    (comp (ref "VR2")
      (value "1K")
      (footprint "eagle-import:TRIM_35WR1KLFTR_V3")
      (fields (field (name "JLC-DNP") "1") (field (name "PARTNUM") "TC33X-2-102E"))
      (libsource (lib "eagle-import") (part "POT-35WR1KLFTR_V3"))
    )
    (comp (ref "VR3")
      (value "1K")
      (footprint "eagle-import:TRIM_35WR1KLFTR_V3")
      (fields (field (name "JLC-DNP") "1") (field (name "PARTNUM") "TC33X-2-102E"))
      (libsource (lib "eagle-import") (part "POT-35WR1KLFTR_V3"))
    )
    (comp (ref "VR4")
      (value "5K")
      (footprint "eagle-import:TRIM_35WR1KLFTR_V2")
      (fields (field (name "JLC-DNP") "1") (field (name "PARTNUM") "TC33X-2-502"))
      (libsource (lib "eagle-import") (part "POT-35WR1KLFTR_V2"))
    )
    (comp (ref "Y1")
      (value "27.12 MHz 10pF")
      (footprint "eagle-import:XTAL-4SMD-3.2X2.5-V2")
      (fields
        (field (name "MF") "Abracon LLC")
        (field (name "MP") "ABM8-27.120MHZ-10-D1G-T")
        (field (name "JLCPARTNUM") "C1986817")
      )
      (libsource (lib "eagle-import") (part "XTAL-4SMD-3.2X2.5-V2"))
    )
  )
  (nets
    (net (code "1") (name "+12V") (class "Default")
      (node (ref "C44") (pin "A") (pinfunction "+_A") (pintype "passive"))
      (node (ref "C61") (pin "A") (pinfunction "+_A") (pintype "passive"))
      (node (ref "D10") (pin "C") (pinfunction "C_C") (pintype "passive"))
      (node (ref "FAN1") (pin "V") (pinfunction "V_V") (pintype "bidirectional"))
      (node (ref "R40") (pin "1") (pinfunction "1_1") (pintype "passive"))
      (node (ref "SJ8") (pin "1") (pinfunction "1_1") (pintype "bidirectional"))
    )
    (net (code "2") (name "+24V") (class "Default")
      (node (ref "L3") (pin "2") (pinfunction "2_2") (pintype "passive"))
      (node (ref "R1") (pin "2") (pinfunction "2_2") (pintype "passive"))
      (node (ref "R2") (pin "2") (pinfunction "2_2") (pintype "passive"))
      (node (ref "R23") (pin "2") (pinfunction "2_2") (pintype "passive"))
      (node (ref "R3") (pin "2") (pinfunction "2_2") (pintype "passive"))
      (node (ref "R42") (pin "1") (pinfunction "1_1") (pintype "passive"))
      (node (ref "TVS6") (pin "C") (pinfunction "2_C") (pintype "passive"))
      (node (ref "U5") (pin "4") (pinfunction "VIN-_4") (pintype "input"))
    )
    (net (code "3") (name "3.3V") (class "Default")
      (node (ref "C45") (pin "A") (pinfunction "+_A") (pintype "passive"))
      (node (ref "C53") (pin "1") (pinfunction "1_1") (pintype "passive"))
      (node (ref "C54") (pin "1") (pinfunction "1_1") (pintype "passive"))
      (node (ref "C57") (pin "2") (pinfunction "2_2") (pintype "passive"))
      (node (ref "D11") (pin "A") (pinfunction "A_A") (pintype "passive"))
      (node (ref "D14") (pin "1") (pinfunction "C_1") (pintype "passive"))
      (node (ref "IC2") (pin "3") (pinfunction "OUT_3") (pintype "output"))
      (node (ref "JP4") (pin "1") (pinfunction "1_1") (pintype "passive"))
      (node (ref "R18") (pin "2") (pinfunction "2_2") (pintype "passive"))
      (node (ref "R19") (pin "1") (pinfunction "1_1") (pintype "passive"))
      (node (ref "R20") (pin "1") (pinfunction "1_1") (pintype "passive"))
      (node (ref "R33") (pin "2") (pinfunction "2_2") (pintype "passive"))
      (node (ref "R35") (pin "2") (pinfunction "2_2") (pintype "passive"))
      (node (ref "R36") (pin "2") (pinfunction "2_2") (pintype "passive"))
      (node (ref "R41") (pin "1") (pinfunction "1_1") (pintype "passive"))
      (node (ref "R50") (pin "2") (pinfunction "2_2") (pintype "passive"))
      (node (ref "R51") (pin "2") (pinfunction "2_2") (pintype "passive"))
      (node (ref "U3") (pin "16") (pinfunction "VDD_16") (pintype "power_in"))
      (node (ref "U3") (pin "5") (pinfunction "VDDA_5") (pintype "power_in"))
      (node (ref "U4") (pin "2") (pinfunction "VCC_2") (pintype "bidirectional"))
      (node (ref "VR2") (pin "1") (pinfunction "A_1") (pintype "passive"))
      (node (ref "VR2") (pin "2") (pinfunction "S_2") (pintype "passive"))
      (node (ref "VR2") (pin "3") (pinfunction "E_3") (pintype "passive"))
    )
    (net (code "4") (name "BTN") (class "Default")
      (node (ref "D12") (pin "1") (pinfunction "C_1") (pintype "passive"))
      (node (ref "SW1") (pin "1") (pinfunction "1_1") (pintype "passive"))
      (node (ref "U3") (pin "13") (pinfunction "PA7/TIM1_CH1N/ADC_IN7_13") (pintype "bidirectional"))
    )
    (net (code "5") (name "BUCK-FB") (class "Default")
      (node (ref "C3") (pin "1") (pinfunction "1_1") (pintype "passive"))
      (node (ref "C8") (pin "2") (pinfunction "2_2") (pintype "passive"))
      (node (ref "D3") (pin "1") (pinfunction "C_1") (pintype "passive"))
      (node (ref "R11") (pin "1") (pinfunction "1_1") (pintype "passive"))
      (node (ref "R37") (pin "1") (pinfunction "1_1") (pintype "passive"))
      (node (ref "R5") (pin "1") (pinfunction "1_1") (pintype "passive"))
      (node (ref "R8") (pin "2") (pinfunction "2_2") (pintype "passive"))
      (node (ref "SJ2") (pin "2") (pinfunction "2_2") (pintype "passive"))
      (node (ref "U1") (pin "5") (pinfunction "FB_5") (pintype "input"))
      (node (ref "VR1") (pin "1") (pinfunction "A_1") (pintype "passive"))
      (node (ref "VR1") (pin "2") (pinfunction "S_2") (pintype "passive"))
    )
    (net (code "6") (name "BUCK-SENS-MCU") (class "Default")
      (node (ref "C47") (pin "1") (pinfunction "1_1") (pintype "passive"))
      (node (ref "R23") (pin "1") (pinfunction "1_1") (pintype "passive"))
      (node (ref "R24") (pin "2") (pinfunction "2_2") (pintype "passive"))
      (node (ref "U3") (pin "9") (pinfunction "PA3/USART1_RX/ADC_IN3_9") (pintype "bidirectional"))
    )
    (net (code "7") (name "CURR-SENS-MCU") (class "Default")
      (node (ref "C49") (pin "1") (pinfunction "1_1") (pintype "passive"))
      (node (ref "R25") (pin "2") (pinfunction "2_2") (pintype "passive"))
      (node (ref "U3") (pin "10") (pinfunction "PA4/TIM14_CH1/ADC_IN4_10") (pintype "bidirectional"))
      (node (ref "U5") (pin "1") (pinfunction "OUT_1") (pintype "output"))
    )
    (net (code "8") (name "CURR-SENS-POSI") (class "Default")
      (node (ref "C4") (pin "1") (pinfunction "+_1") (pintype "passive"))
      (node (ref "C4") (pin "1B") (pinfunction "+_1B") (pintype "passive"))
      (node (ref "C46") (pin "2") (pinfunction "2_2") (pintype "passive"))
      (node (ref "L2") (pin "2") (pinfunction "2_2") (pintype "passive"))
      (node (ref "R1") (pin "1") (pinfunction "1_1") (pintype "passive"))
      (node (ref "R2") (pin "1") (pinfunction "1_1") (pintype "passive"))
      (node (ref "R3") (pin "1") (pinfunction "1_1") (pintype "passive"))
      (node (ref "U5") (pin "3") (pinfunction "VIN+_3") (pintype "input"))
      (node (ref "U5") (pin "5") (pinfunction "V+_5") (pintype "power_in"))
    )
    (net (code "9") (name "DC-IN") (class "Default")
      (node (ref "C43") (pin "A") (pinfunction "+_A") (pintype "passive"))
      (node (ref "C5") (pin "A") (pinfunction "+_A") (pintype "passive"))
      (node (ref "C6") (pin "1") (pinfunction "+_1") (pintype "passive"))
      (node (ref "D11") (pin "C") (pinfunction "C_C") (pintype "passive"))
      (node (ref "D13") (pin "C") (pinfunction "C_C") (pintype "passive"))
      (node (ref "F1") (pin "3") (pinfunction "2_3") (pintype "bidirectional"))
      (node (ref "F1") (pin "4") (pinfunction "2_4") (pintype "bidirectional"))
      (node (ref "IC1") (pin "1") (pinfunction "IN_1") (pintype "input"))
      (node (ref "IC2") (pin "1") (pinfunction "IN_1") (pintype "input"))
      (node (ref "R26") (pin "2") (pinfunction "2_2") (pintype "passive"))
      (node (ref "R38") (pin "1") (pinfunction "1_1") (pintype "passive"))
      (node (ref "U1") (pin "2") (pinfunction "VIN_2") (pintype "input"))
    )
    (net (code "10") (name "DC-SENS-MCU") (class "Default")
      (node (ref "C48") (pin "1") (pinfunction "1_1") (pintype "passive"))
      (node (ref "R26") (pin "1") (pinfunction "1_1") (pintype "passive"))
      (node (ref "R27") (pin "2") (pinfunction "2_2") (pintype "passive"))
      (node (ref "U3") (pin "6") (pinfunction "PA0/ADC_IN0_6") (pintype "bidirectional"))
    )
    (net (code "11") (name "DC-SRC") (class "Default")
      (node (ref "F1") (pin "1") (pinfunction "1_1") (pintype "bidirectional"))
      (node (ref "F1") (pin "2") (pinfunction "1_2") (pintype "bidirectional"))
      (node (ref "Q5") (pin "1") (pinfunction "S_1") (pintype "passive"))
      (node (ref "Q5") (pin "2") (pinfunction "S_2") (pintype "passive"))
      (node (ref "Q5") (pin "3") (pinfunction "S_3") (pintype "passive"))
      (node (ref "Q7") (pin "5") (pinfunction "D_5") (pintype "passive"))
      (node (ref "Q7") (pin "6") (pinfunction "D_6") (pintype "passive"))
      (node (ref "Q7") (pin "7") (pinfunction "D_7") (pintype "passive"))
      (node (ref "Q7") (pin "8") (pinfunction "D_8") (pintype "passive"))
      (node (ref "Q7") (pin "9") (pinfunction "D_9") (pintype "passive"))
      (node (ref "U6") (pin "9") (pinfunction "OUT_9") (pintype "passive"))
    )
    (net (code "12") (name "FAN-CTRL-SIG") (class "Default")
      (node (ref "R44") (pin "1") (pinfunction "1_1") (pintype "passive"))
      (node (ref "R45") (pin "1") (pinfunction "1_1") (pintype "passive"))
      (node (ref "SJ3") (pin "1") (pinfunction "1_1") (pintype "passive"))
      (node (ref "SJ5") (pin "3") (pinfunction "3_3") (pintype "passive"))
    )
    (net (code "13") (name "GND") (class "Default")
      (node (ref "C13") (pin "2") (pinfunction "2_2") (pintype "passive"))
      (node (ref "C14") (pin "2") (pinfunction "2_2") (pintype "passive"))
      (node (ref "C15") (pin "2") (pinfunction "2_2") (pintype "passive"))
      (node (ref "C16") (pin "2") (pinfunction "2_2") (pintype "passive"))
      (node (ref "C17") (pin "2") (pinfunction "2_2") (pintype "passive"))
      (node (ref "C18") (pin "2") (pinfunction "2_2") (pintype "passive"))
      (node (ref "C19") (pin "2") (pinfunction "2_2") (pintype "passive"))
      (node (ref "C2") (pin "2") (pinfunction "-_2") (pintype "passive"))
      (node (ref "C2") (pin "2B") (pinfunction "-_2B") (pintype "passive"))
      (node (ref "C20") (pin "2") (pinfunction "2_2") (pintype "passive"))
      (node (ref "C21") (pin "2") (pinfunction "2_2") (pintype "passive"))
      (node (ref "C22") (pin "2") (pinfunction "2_2") (pintype "passive"))
      (node (ref "C23") (pin "2") (pinfunction "2_2") (pintype "passive"))
      (node (ref "C24") (pin "2") (pinfunction "2_2") (pintype "passive"))
      (node (ref "C25") (pin "2") (pinfunction "2_2") (pintype "passive"))
      (node (ref "C26") (pin "2") (pinfunction "2_2") (pintype "passive"))
      (node (ref "C27") (pin "2") (pinfunction "2_2") (pintype "passive"))
      (node (ref "C28") (pin "2") (pinfunction "2_2") (pintype "passive"))
      (node (ref "C29") (pin "2") (pinfunction "2_2") (pintype "passive"))
      (node (ref "C30") (pin "2") (pinfunction "2_2") (pintype "passive"))
      (node (ref "C31") (pin "2") (pinfunction "2_2") (pintype "passive"))
      (node (ref "C32") (pin "2") (pinfunction "2_2") (pintype "passive"))
      (node (ref "C34") (pin "2") (pinfunction "2_2") (pintype "passive"))
      (node (ref "C35") (pin "1") (pinfunction "1_1") (pintype "passive"))
      (node (ref "C36") (pin "1") (pinfunction "1_1") (pintype "passive"))
      (node (ref "C39") (pin "2") (pinfunction "2_2") (pintype "passive"))
      (node (ref "C4") (pin "2") (pinfunction "-_2") (pintype "passive"))
      (node (ref "C4") (pin "2B") (pinfunction "-_2B") (pintype "passive"))
      (node (ref "C40") (pin "2") (pinfunction "2_2") (pintype "passive"))
      (node (ref "C41") (pin "2") (pinfunction "2_2") (pintype "passive"))
      (node (ref "C42") (pin "2") (pinfunction "2_2") (pintype "passive"))
      (node (ref "C43") (pin "C") (pinfunction "-_C") (pintype "passive"))
      (node (ref "C44") (pin "C") (pinfunction "-_C") (pintype "passive"))
      (node (ref "C45") (pin "C") (pinfunction "-_C") (pintype "passive"))
      (node (ref "C46") (pin "1") (pinfunction "1_1") (pintype "passive"))
      (node (ref "C47") (pin "2") (pinfunction "2_2") (pintype "passive"))
      (node (ref "C48") (pin "2") (pinfunction "2_2") (pintype "passive"))
      (node (ref "C49") (pin "2") (pinfunction "2_2") (pintype "passive"))
      (node (ref "C5") (pin "C") (pinfunction "-_C") (pintype "passive"))
      (node (ref "C50") (pin "2") (pinfunction "2_2") (pintype "passive"))
      (node (ref "C52") (pin "2") (pinfunction "2_2") (pintype "passive"))
      (node (ref "C53") (pin "2") (pinfunction "2_2") (pintype "passive"))
      (node (ref "C54") (pin "2") (pinfunction "2_2") (pintype "passive"))
      (node (ref "C55") (pin "2") (pinfunction "2_2") (pintype "passive"))
      (node (ref "C56") (pin "2") (pinfunction "2_2") (pintype "passive"))
      (node (ref "C57") (pin "1") (pinfunction "1_1") (pintype "passive"))
      (node (ref "C58") (pin "1") (pinfunction "1_1") (pintype "passive"))
      (node (ref "C59") (pin "2") (pinfunction "2_2") (pintype "passive"))
      (node (ref "C6") (pin "2") (pinfunction "-_2") (pintype "passive"))
      (node (ref "C60") (pin "2") (pinfunction "2_2") (pintype "passive"))
      (node (ref "C61") (pin "C") (pinfunction "-_C") (pintype "passive"))
      (node (ref "C63") (pin "1") (pinfunction "1_1") (pintype "passive"))
      (node (ref "C64") (pin "1") (pinfunction "1_1") (pintype "passive"))
      (node (ref "C8") (pin "1") (pinfunction "1_1") (pintype "passive"))
      (node (ref "D1") (pin "A") (pinfunction "A_A") (pintype "passive"))
      (node (ref "D12") (pin "2") (pinfunction "A_2") (pintype "passive"))
      (node (ref "D14") (pin "2") (pinfunction "A_2") (pintype "passive"))
      (node (ref "D7") (pin "A") (pinfunction "A_A") (pintype "passive"))
      (node (ref "D8") (pin "C") (pinfunction "C_C") (pintype "passive"))
      (node (ref "D9") (pin "A") (pinfunction "A_A") (pintype "passive"))
      (node (ref "IC1") (pin "2") (pinfunction "GND_2") (pintype "input"))
      (node (ref "IC2") (pin "2") (pinfunction "GND_2") (pintype "input"))
      (node (ref "JP1") (pin "2") (pinfunction "GND_2_2") (pintype "passive"))
      (node (ref "JP1") (pin "3") (pinfunction "GND_3_3") (pintype "passive"))
      (node (ref "JP1") (pin "4") (pinfunction "GND_4_4") (pintype "passive"))
      (node (ref "JP1") (pin "5") (pinfunction "GND_5") (pintype "passive"))
      (node (ref "JP2") (pin "A12") (pinfunction "GND_A12") (pintype "passive"))
      (node (ref "JP2") (pin "B12") (pinfunction "GND_B12") (pintype "passive"))
      (node (ref "JP2") (pin "M1") (pinfunction "SHIELD_M1") (pintype "passive"))
      (node (ref "JP2") (pin "M2") (pinfunction "SHIELD_M2") (pintype "passive"))
      (node (ref "JP2") (pin "M3") (pinfunction "SHIELD_M3") (pintype "passive"))
      (node (ref "JP2") (pin "M4") (pinfunction "SHIELD_M4") (pintype "passive"))
      (node (ref "JP3") (pin "M1") (pinfunction "M1_M1") (pintype "bidirectional"))
      (node (ref "JP3") (pin "M2") (pinfunction "M2_M2") (pintype "bidirectional"))
      (node (ref "JP3") (pin "N") (pinfunction "N_N") (pintype "bidirectional"))
      (node (ref "JP4") (pin "3") (pinfunction "3_3") (pintype "passive"))
      (node (ref "JP5") (pin "2") (pinfunction "2_2") (pintype "passive"))
      (node (ref "JP5") (pin "3") (pinfunction "3_3") (pintype "passive"))
      (node (ref "JP5") (pin "5") (pinfunction "5_5") (pintype "passive"))
      (node (ref "JP5") (pin "6") (pinfunction "6_6") (pintype "passive"))
      (node (ref "LED1") (pin "C") (pinfunction "C_C") (pintype "passive"))
      (node (ref "LED2") (pin "C") (pinfunction "C_C") (pintype "passive"))
      (node (ref "LED3") (pin "C") (pinfunction "C_C") (pintype "passive"))
      (node (ref "LED4") (pin "C") (pinfunction "C_C") (pintype "passive"))
      (node (ref "PCB1") (pin "1") (pinfunction "1_1") (pintype "bidirectional"))
      (node (ref "PCB1") (pin "2") (pinfunction "1_2") (pintype "bidirectional"))
      (node (ref "PCB1") (pin "3") (pinfunction "1_3") (pintype "bidirectional"))
      (node (ref "PCB1") (pin "4") (pinfunction "1_4") (pintype "bidirectional"))
      (node (ref "Q2") (pin "3") (pinfunction "S_3") (pintype "passive"))
      (node (ref "Q3") (pin "2") (pinfunction "E_2") (pintype "passive"))
      (node (ref "Q8") (pin "2") (pinfunction "S_2") (pintype "passive"))
      (node (ref "Q9") (pin "2") (pinfunction "S_2") (pintype "passive"))
      (node (ref "R12") (pin "1") (pinfunction "1_1") (pintype "passive"))
      (node (ref "R13") (pin "1") (pinfunction "1_1") (pintype "passive"))
      (node (ref "R15") (pin "1") (pinfunction "1_1") (pintype "passive"))
      (node (ref "R24") (pin "1") (pinfunction "1_1") (pintype "passive"))
      (node (ref "R25") (pin "1") (pinfunction "1_1") (pintype "passive"))
      (node (ref "R27") (pin "1") (pinfunction "1_1") (pintype "passive"))
      (node (ref "R28") (pin "1") (pinfunction "1_1") (pintype "passive"))
      (node (ref "R44") (pin "2") (pinfunction "2_2") (pintype "passive"))
      (node (ref "R46B") (pin "2") (pinfunction "2_2") (pintype "passive"))
      (node (ref "R47") (pin "2") (pinfunction "2_2") (pintype "passive"))
      (node (ref "R54") (pin "2") (pinfunction "2_2") (pintype "passive"))
      (node (ref "R55") (pin "2") (pinfunction "2_2") (pintype "passive"))
      (node (ref "R6") (pin "1") (pinfunction "1_1") (pintype "passive"))
      (node (ref "R7") (pin "1") (pinfunction "1_1") (pintype "passive"))
      (node (ref "R8") (pin "1") (pinfunction "1_1") (pintype "passive"))
      (node (ref "SJ1") (pin "1") (pinfunction "1_1") (pintype "passive"))
      (node (ref "SJ4") (pin "1") (pinfunction "1_1") (pintype "passive"))
      (node (ref "SJ6") (pin "1") (pinfunction "1_1") (pintype "bidirectional"))
      (node (ref "SJ7") (pin "1") (pinfunction "1_1") (pintype "bidirectional"))
      (node (ref "STANDOFF1") (pin "1") (pinfunction "1_1") (pintype "bidirectional"))
      (node (ref "STANDOFF1") (pin "2") (pinfunction "1_2") (pintype "bidirectional"))
      (node (ref "STANDOFF2") (pin "1") (pinfunction "1_1") (pintype "bidirectional"))
      (node (ref "STANDOFF2") (pin "2") (pinfunction "1_2") (pintype "bidirectional"))
      (node (ref "SW1") (pin "2") (pinfunction "2_2") (pintype "passive"))
      (node (ref "SW1") (pin "S1") (pinfunction "MNT_S1") (pintype "power_in"))
      (node (ref "SW1") (pin "S2") (pinfunction "MNT_S2") (pintype "power_in"))
      (node (ref "THERM1") (pin "2") (pinfunction "2_2") (pintype "passive"))
      (node (ref "THERM2") (pin "2") (pinfunction "2_2") (pintype "passive"))
      (node (ref "TVS1") (pin "A") (pinfunction "1_A") (pintype "passive"))
      (node (ref "TVS2") (pin "A") (pinfunction "1_A") (pintype "passive"))
      (node (ref "TVS3") (pin "A") (pinfunction "1_A") (pintype "passive"))
      (node (ref "TVS4") (pin "2") (pinfunction "1_2") (pintype "passive"))
      (node (ref "TVS5") (pin "A") (pinfunction "1_A") (pintype "passive"))
      (node (ref "TVS6") (pin "A") (pinfunction "1_A") (pintype "passive"))
      (node (ref "U1") (pin "10") (pinfunction "GND_10") (pintype "power_in"))
      (node (ref "U1") (pin "11") (pinfunction "GND_11") (pintype "power_in"))
      (node (ref "U1") (pin "12") (pinfunction "GND_12") (pintype "power_in"))
      (node (ref "U1") (pin "13") (pinfunction "GND_13") (pintype "power_in"))
      (node (ref "U1") (pin "14") (pinfunction "GND_14") (pintype "power_in"))
      (node (ref "U1") (pin "15") (pinfunction "GND_15") (pintype "power_in"))
      (node (ref "U1") (pin "16") (pinfunction "GND_16") (pintype "power_in"))
      (node (ref "U1") (pin "17") (pinfunction "GND_17") (pintype "power_in"))
      (node (ref "U1") (pin "7") (pinfunction "GND_7") (pintype "power_in"))
      (node (ref "U1") (pin "9") (pinfunction "GND_9") (pintype "power_in"))
      (node (ref "U2") (pin "4") (pinfunction "GND_4") (pintype "power_in"))
      (node (ref "U2") (pin "5") (pinfunction "IN_N_5") (pintype "input"))
      (node (ref "U3") (pin "15") (pinfunction "VSS_15") (pintype "power_in"))
      (node (ref "U4") (pin "1") (pinfunction "GND_1") (pintype "bidirectional"))
      (node (ref "U5") (pin "2") (pinfunction "GND_2") (pintype "power_in"))
      (node (ref "U6") (pin "7") (pinfunction "GND_7") (pintype "power_in"))
      (node (ref "U7") (pin "2") (pinfunction "ISNP_2") (pintype "bidirectional"))
      (node (ref "U7") (pin "3") (pinfunction "GND_3") (pintype "bidirectional"))
      (node (ref "U7") (pin "8") (pinfunction "PDOSEL_8") (pintype "bidirectional"))
      (node (ref "U7") (pin "EXP") (pinfunction "GND_EXP") (pintype "bidirectional"))
      (node (ref "Y1") (pin "2") (pinfunction "GND_2") (pintype "power_in"))
      (node (ref "Y1") (pin "4") (pinfunction "GND_4") (pintype "power_in"))
    )
    (net (code "14") (name "NRST") (class "Default")
      (node (ref "JP4") (pin "5") (pinfunction "5_5") (pintype "passive"))
      (node (ref "R33") (pin "1") (pinfunction "1_1") (pintype "passive"))
      (node (ref "U3") (pin "4") (pinfunction "NRST_4") (pintype "bidirectional"))
    )
    (net (code "15") (name "Net-(C2-+-Pad1)") (class "Default")
      (node (ref "C2") (pin "1") (pinfunction "+_1") (pintype "passive"))
      (node (ref "C2") (pin "1B") (pinfunction "+_1B") (pintype "passive"))
      (node (ref "C3") (pin "2") (pinfunction "2_2") (pintype "passive"))
      (node (ref "D2") (pin "C") (pinfunction "C_C") (pintype "passive"))
      (node (ref "L1") (pin "2") (pinfunction "2_2") (pintype "passive"))
      (node (ref "L1") (pin "2B") (pinfunction "2_2B") (pintype "passive"))
      (node (ref "L2") (pin "1") (pinfunction "1_1") (pintype "passive"))
      (node (ref "R4") (pin "2") (pinfunction "2_2") (pintype "passive"))
    )
    (net (code "16") (name "Net-(C7-Pad1)") (class "Default")
      (node (ref "C7") (pin "1") (pinfunction "1_1") (pintype "passive"))
      (node (ref "R7") (pin "2") (pinfunction "2_2") (pintype "passive"))
    )
    (net (code "17") (name "Net-(C10-Pad2)") (class "Default")
      (node (ref "C10") (pin "2") (pinfunction "2_2") (pintype "passive"))
      (node (ref "C11") (pin "2") (pinfunction "2_2") (pintype "passive"))
      (node (ref "C12") (pin "2") (pinfunction "2_2") (pintype "passive"))
      (node (ref "C9") (pin "2") (pinfunction "2_2") (pintype "passive"))
      (node (ref "L4") (pin "1") (pinfunction "1_1") (pintype "passive"))
    )
    (net (code "18") (name "Net-(C13-Pad1)") (class "Default")
      (node (ref "C13") (pin "1") (pinfunction "1_1") (pintype "passive"))
      (node (ref "C14") (pin "1") (pinfunction "1_1") (pintype "passive"))
      (node (ref "C15") (pin "1") (pinfunction "1_1") (pintype "passive"))
      (node (ref "C16") (pin "1") (pinfunction "1_1") (pintype "passive"))
      (node (ref "C17") (pin "1") (pinfunction "1_1") (pintype "passive"))
      (node (ref "C18") (pin "1") (pinfunction "1_1") (pintype "passive"))
      (node (ref "C19") (pin "1") (pinfunction "1_1") (pintype "passive"))
      (node (ref "L4") (pin "2") (pinfunction "2_2") (pintype "passive"))
      (node (ref "L5") (pin "1") (pinfunction "1_1") (pintype "passive"))
    )
    (net (code "19") (name "Net-(C20-Pad1)") (class "Default")
      (node (ref "C20") (pin "1") (pinfunction "1_1") (pintype "passive"))
      (node (ref "C21") (pin "1") (pinfunction "1_1") (pintype "passive"))
      (node (ref "C22") (pin "1") (pinfunction "1_1") (pintype "passive"))
      (node (ref "C23") (pin "1") (pinfunction "1_1") (pintype "passive"))
      (node (ref "C24") (pin "1") (pinfunction "1_1") (pintype "passive"))
      (node (ref "C25") (pin "1") (pinfunction "1_1") (pintype "passive"))
      (node (ref "C26") (pin "1") (pinfunction "1_1") (pintype "passive"))
      (node (ref "L5") (pin "2") (pinfunction "2_2") (pintype "passive"))
      (node (ref "L6") (pin "1") (pinfunction "1_1") (pintype "passive"))
    )
    (net (code "20") (name "Net-(C37-Pad2)") (class "Default")
      (node (ref "C37") (pin "2") (pinfunction "2_2") (pintype "passive"))
      (node (ref "C38") (pin "2") (pinfunction "2_2") (pintype "passive"))
      (node (ref "L8") (pin "1") (pinfunction "1_1") (pintype "passive"))
    )
    (net (code "21") (name "Net-(C42-Pad1)") (class "Default")
      (node (ref "C42") (pin "1") (pinfunction "1_1") (pintype "passive"))
      (node (ref "L9") (pin "2") (pinfunction "2_2") (pintype "passive"))
      (node (ref "R19") (pin "2") (pinfunction "2_2") (pintype "passive"))
      (node (ref "R20") (pin "2") (pinfunction "2_2") (pintype "passive"))
      (node (ref "R22") (pin "2") (pinfunction "2_2") (pintype "passive"))
    )
    (net (code "22") (name "Net-(C62-Pad1)") (class "Default")
      (node (ref "C62") (pin "1") (pinfunction "1_1") (pintype "passive"))
      (node (ref "C63") (pin "2") (pinfunction "2_2") (pintype "passive"))
    )
    (net (code "23") (name "Net-(C62-Pad2)") (class "Default")
      (node (ref "C62") (pin "2") (pinfunction "2_2") (pintype "passive"))
      (node (ref "R56") (pin "2") (pinfunction "2_2") (pintype "passive"))
    )
    (net (code "24") (name "Net-(D2-PadA)") (class "Default")
      (node (ref "D2") (pin "A") (pinfunction "A_A") (pintype "passive"))
      (node (ref "R5") (pin "2") (pinfunction "2_2") (pintype "passive"))
    )
    (net (code "25") (name "Net-(D3-A)") (class "Default")
      (node (ref "C58") (pin "2") (pinfunction "2_2") (pintype "passive"))
      (node (ref "D3") (pin "2") (pinfunction "A_2") (pintype "passive"))
      (node (ref "R9") (pin "2") (pinfunction "2_2") (pintype "passive"))
    )
    (net (code "26") (name "Net-(D5-PadC)") (class "Default")
      (node (ref "D5") (pin "C") (pinfunction "C_C") (pintype "passive"))
      (node (ref "D6") (pin "A") (pinfunction "A_A") (pintype "passive"))
      (node (ref "R10") (pin "1") (pinfunction "1_1") (pintype "passive"))
    )
    (net (code "27") (name "Net-(FAN1-PadG)") (class "Default")
      (node (ref "FAN1") (pin "G") (pinfunction "G_G") (pintype "bidirectional"))
      (node (ref "SJ4") (pin "2") (pinfunction "2_2") (pintype "passive"))
    )
    (net (code "28") (name "Net-(FAN1-PadP)") (class "Default")
      (node (ref "FAN1") (pin "P") (pinfunction "P_P") (pintype "bidirectional"))
      (node (ref "SJ5") (pin "2") (pinfunction "2_2") (pintype "passive"))
    )
    (net (code "29") (name "Net-(IC1-OUT)") (class "Default")
      (node (ref "D10") (pin "A") (pinfunction "A_A") (pintype "passive"))
      (node (ref "IC1") (pin "3") (pinfunction "OUT_3") (pintype "output"))
    )
    (net (code "30") (name "Net-(JP2-CC1)") (class "Default")
      (node (ref "JP2") (pin "A5") (pinfunction "CC1_A5") (pintype "passive"))
      (node (ref "U7") (pin "11") (pinfunction "CC1_11") (pintype "bidirectional"))
    )
    (net (code "31") (name "Net-(JP2-CC2)") (class "Default")
      (node (ref "JP2") (pin "B5") (pinfunction "CC2_B5") (pintype "passive"))
      (node (ref "U7") (pin "12") (pinfunction "CC2_12") (pintype "bidirectional"))
    )
    (net (code "32") (name "Net-(JP5-Pad4)") (class "Default")
      (node (ref "JP5") (pin "4") (pinfunction "4_4") (pintype "passive"))
      (node (ref "R49") (pin "2") (pinfunction "2_2") (pintype "passive"))
    )
    (net (code "33") (name "Net-(L9-Pad1)") (class "Default")
      (node (ref "L9") (pin "1") (pinfunction "1_1") (pintype "passive"))
      (node (ref "R21") (pin "2") (pinfunction "2_2") (pintype "passive"))
    )
    (net (code "34") (name "Net-(LED1-PadA)") (class "Default")
      (node (ref "LED1") (pin "A") (pinfunction "A_A") (pintype "passive"))
      (node (ref "R38") (pin "2") (pinfunction "2_2") (pintype "passive"))
      (node (ref "R39") (pin "1") (pinfunction "1_1") (pintype "passive"))
      (node (ref "R39") (pin "2") (pinfunction "2_2") (pintype "passive"))
    )
    (net (code "35") (name "Net-(LED2-PadA)") (class "Default")
      (node (ref "LED2") (pin "A") (pinfunction "A_A") (pintype "passive"))
      (node (ref "R40") (pin "2") (pinfunction "2_2") (pintype "passive"))
    )
    (net (code "36") (name "Net-(LED3-PadA)") (class "Default")
      (node (ref "LED3") (pin "A") (pinfunction "A_A") (pintype "passive"))
      (node (ref "R41") (pin "2") (pinfunction "2_2") (pintype "passive"))
    )
    (net (code "37") (name "Net-(LED4-PadA)") (class "Default")
      (node (ref "LED4") (pin "A") (pinfunction "A_A") (pintype "passive"))
      (node (ref "R42") (pin "2") (pinfunction "2_2") (pintype "passive"))
      (node (ref "R43") (pin "1") (pinfunction "1_1") (pintype "passive"))
      (node (ref "R43") (pin "2") (pinfunction "2_2") (pintype "passive"))
    )
    (net (code "38") (name "Net-(Q1-D)") (class "Default")
      (node (ref "C10") (pin "1") (pinfunction "1_1") (pintype "passive"))
      (node (ref "C11") (pin "1") (pinfunction "1_1") (pintype "passive"))
      (node (ref "C12") (pin "1") (pinfunction "1_1") (pintype "passive"))
      (node (ref "C9") (pin "1") (pinfunction "1_1") (pintype "passive"))
      (node (ref "D4") (pin "A") (pinfunction "A_A") (pintype "passive"))
      (node (ref "L3") (pin "1") (pinfunction "1_1") (pintype "passive"))
      (node (ref "Q1") (pin "2") (pinfunction "D_2") (pintype "passive"))
    )
    (net (code "39") (name "Net-(Q1-S)") (class "Default")
      (node (ref "Q1") (pin "3") (pinfunction "S_3") (pintype "passive"))
      (node (ref "SJ6") (pin "2") (pinfunction "2_2") (pintype "bidirectional"))
      (node (ref "SJ7") (pin "2") (pinfunction "2_2") (pintype "bidirectional"))
    )
    (net (code "40") (name "Net-(Q2-D)") (class "Default")
      (node (ref "C37") (pin "1") (pinfunction "1_1") (pintype "passive"))
      (node (ref "C38") (pin "1") (pinfunction "1_1") (pintype "passive"))
      (node (ref "C39") (pin "1") (pinfunction "1_1") (pintype "passive"))
      (node (ref "C40") (pin "1") (pinfunction "1_1") (pintype "passive"))
      (node (ref "L7") (pin "1") (pinfunction "1_1") (pintype "passive"))
      (node (ref "Q2") (pin "2") (pinfunction "D_2") (pintype "passive"))
    )
    (net (code "41") (name "Net-(Q2-G)") (class "Default")
      (node (ref "Q2") (pin "1") (pinfunction "G_1") (pintype "passive"))
      (node (ref "R16") (pin "2") (pinfunction "2_2") (pintype "passive"))
      (node (ref "R17") (pin "2") (pinfunction "2_2") (pintype "passive"))
    )
    (net (code "42") (name "Net-(Q3-B)") (class "Default")
      (node (ref "Q3") (pin "1") (pinfunction "B_1") (pintype "passive"))
      (node (ref "R22") (pin "1") (pinfunction "1_1") (pintype "passive"))
      (node (ref "VR3") (pin "1") (pinfunction "A_1") (pintype "passive"))
      (node (ref "VR3") (pin "2") (pinfunction "S_2") (pintype "passive"))
      (node (ref "VR3") (pin "3") (pinfunction "E_3") (pintype "passive"))
    )
    (net (code "43") (name "Net-(Q4-G)") (class "Default")
      (node (ref "Q4") (pin "4") (pinfunction "G_4") (pintype "passive"))
      (node (ref "U6") (pin "1") (pinfunction "DGATE_1") (pintype "output"))
    )
    (net (code "44") (name "Net-(Q5-G)") (class "Default")
      (node (ref "Q5") (pin "4") (pinfunction "G_4") (pintype "passive"))
      (node (ref "R56") (pin "1") (pinfunction "1_1") (pintype "passive"))
      (node (ref "U6") (pin "8") (pinfunction "HGATE_8") (pintype "output"))
    )
    (net (code "45") (name "Net-(Q6A-G)") (class "Default")
      (node (ref "Q6") (pin "2") (pinfunction "G_2") (pintype "passive"))
      (node (ref "Q6") (pin "4") (pinfunction "G_4") (pintype "passive"))
      (node (ref "Q7") (pin "4") (pinfunction "G_4") (pintype "passive"))
      (node (ref "R30") (pin "1") (pinfunction "1_1") (pintype "passive"))
    )
    (net (code "46") (name "Net-(Q6A-S)") (class "Default")
      (node (ref "Q6") (pin "1") (pinfunction "S_1") (pintype "passive"))
      (node (ref "Q7") (pin "1") (pinfunction "S_1") (pintype "passive"))
      (node (ref "Q7") (pin "2") (pinfunction "S_2") (pintype "passive"))
      (node (ref "Q7") (pin "3") (pinfunction "S_3") (pintype "passive"))
      (node (ref "R32") (pin "1") (pinfunction "1_1") (pintype "passive"))
    )
    (net (code "47") (name "Net-(Q6B-S)") (class "Default")
      (node (ref "JP2") (pin "A9") (pinfunction "VBUS_A9") (pintype "passive"))
      (node (ref "JP2") (pin "B9") (pinfunction "VBUS_B9") (pintype "passive"))
      (node (ref "Q6") (pin "3") (pinfunction "S_3") (pintype "passive"))
      (node (ref "R29") (pin "1") (pinfunction "1_1") (pintype "passive"))
      (node (ref "TVS5") (pin "C") (pinfunction "2_C") (pintype "passive"))
      (node (ref "U7") (pin "1") (pinfunction "VCC2_1") (pintype "bidirectional"))
    )
    (net (code "48") (name "Net-(Q8-D)") (class "Default")
      (node (ref "Q8") (pin "3") (pinfunction "D_3") (pintype "passive"))
      (node (ref "R34") (pin "1") (pinfunction "1_1") (pintype "passive"))
      (node (ref "U6") (pin "6") (pinfunction "EN_UVLO_6") (pintype "passive"))
    )
    (net (code "49") (name "Net-(Q8-G)") (class "Default")
      (node (ref "Q8") (pin "1") (pinfunction "G_1") (pintype "passive"))
      (node (ref "R28") (pin "2") (pinfunction "2_2") (pintype "passive"))
      (node (ref "R29") (pin "2") (pinfunction "2_2") (pintype "passive"))
      (node (ref "TVS4") (pin "1") (pinfunction "2_1") (pintype "passive"))
    )
    (net (code "50") (name "Net-(Q9-D)") (class "Default")
      (node (ref "Q9") (pin "3") (pinfunction "D_3") (pintype "passive"))
      (node (ref "SJ4") (pin "3") (pinfunction "3_3") (pintype "passive"))
      (node (ref "SJ5") (pin "1") (pinfunction "1_1") (pintype "passive"))
    )
    (net (code "51") (name "Net-(Q9-G)") (class "Default")
      (node (ref "Q9") (pin "1") (pinfunction "G_1") (pintype "passive"))
      (node (ref "R45") (pin "2") (pinfunction "2_2") (pintype "passive"))
    )
    (net (code "52") (name "Net-(R31-Pad1)") (class "Default")
      (node (ref "R31") (pin "1") (pinfunction "1_1") (pintype "passive"))
      (node (ref "R32") (pin "2") (pinfunction "2_2") (pintype "passive"))
    )
    (net (code "53") (name "Net-(R46-Pad2)") (class "Default")
      (node (ref "R46") (pin "2") (pinfunction "2_2") (pintype "passive"))
      (node (ref "R46B") (pin "1") (pinfunction "1_1") (pintype "passive"))
    )
    (net (code "54") (name "Net-(R48-Pad2)") (class "Default")
      (node (ref "R48") (pin "2") (pinfunction "2_2") (pintype "passive"))
      (node (ref "R49") (pin "1") (pinfunction "1_1") (pintype "passive"))
    )
    (net (code "55") (name "Net-(T1-1)") (class "Default")
      (node (ref "D5") (pin "A") (pinfunction "A_A") (pintype "passive"))
      (node (ref "D7") (pin "C") (pinfunction "C_C") (pintype "passive"))
      (node (ref "T1") (pin "S1A") (pinfunction "1_S1A") (pintype "bidirectional"))
    )
    (net (code "56") (name "Net-(T1-2)") (class "Default")
      (node (ref "D6") (pin "C") (pinfunction "C_C") (pintype "passive"))
      (node (ref "D8") (pin "A") (pinfunction "A_A") (pintype "passive"))
      (node (ref "T1") (pin "S2B") (pinfunction "2_S2B") (pintype "bidirectional"))
    )
    (net (code "57") (name "Net-(T1-3)") (class "Default")
      (node (ref "C33") (pin "2") (pinfunction "2_2") (pintype "passive"))
      (node (ref "T1") (pin "S1B") (pinfunction "4_S1B") (pintype "bidirectional"))
      (node (ref "T1") (pin "S2A") (pinfunction "3_S2A") (pintype "bidirectional"))
    )
    (net (code "58") (name "Net-(T1-P2)") (class "Default")
      (node (ref "C27") (pin "1") (pinfunction "1_1") (pintype "passive"))
      (node (ref "C28") (pin "1") (pinfunction "1_1") (pintype "passive"))
      (node (ref "C29") (pin "1") (pinfunction "1_1") (pintype "passive"))
      (node (ref "C30") (pin "1") (pinfunction "1_1") (pintype "passive"))
      (node (ref "C31") (pin "1") (pinfunction "1_1") (pintype "passive"))
      (node (ref "C32") (pin "1") (pinfunction "1_1") (pintype "passive"))
      (node (ref "L6") (pin "2") (pinfunction "2_2") (pintype "passive"))
      (node (ref "T1") (pin "P1") (pinfunction "P2_P1") (pintype "bidirectional"))
    )
    (net (code "59") (name "Net-(TVS1-2)") (class "Default")
      (node (ref "D4") (pin "C") (pinfunction "C_C") (pintype "passive"))
      (node (ref "TVS1") (pin "C") (pinfunction "2_C") (pintype "passive"))
    )
    (net (code "60") (name "Net-(TVS3-2)") (class "Default")
      (node (ref "C50") (pin "1") (pinfunction "1_1") (pintype "passive"))
      (node (ref "JP3") (pin "P") (pinfunction "P_P") (pintype "bidirectional"))
      (node (ref "Q4") (pin "1") (pinfunction "S_1") (pintype "passive"))
      (node (ref "Q4") (pin "2") (pinfunction "S_2") (pintype "passive"))
      (node (ref "Q4") (pin "3") (pinfunction "S_3") (pintype "passive"))
      (node (ref "TVS3") (pin "C") (pinfunction "2_C") (pintype "passive"))
      (node (ref "U6") (pin "2") (pinfunction "A_2") (pintype "passive"))
      (node (ref "U6") (pin "3") (pinfunction "VSNS_3") (pintype "passive"))
    )
    (net (code "61") (name "Net-(U1-BOOT)") (class "Default")
      (node (ref "C1") (pin "1") (pinfunction "1_1") (pintype "passive"))
      (node (ref "U1") (pin "1") (pinfunction "BOOT_1") (pintype "output"))
    )
    (net (code "62") (name "Net-(U1-COMP)") (class "Default")
      (node (ref "C7") (pin "2") (pinfunction "2_2") (pintype "passive"))
      (node (ref "U1") (pin "6") (pinfunction "COMP_6") (pintype "output"))
    )
    (net (code "63") (name "Net-(U1-RT{slash}CLK)") (class "Default")
      (node (ref "R6") (pin "2") (pinfunction "2_2") (pintype "passive"))
      (node (ref "U1") (pin "4") (pinfunction "RT/CLK_4") (pintype "input"))
    )
    (net (code "64") (name "Net-(U1-SW)") (class "Default")
      (node (ref "C1") (pin "2") (pinfunction "2_2") (pintype "passive"))
      (node (ref "D1") (pin "C") (pinfunction "C_C") (pintype "passive"))
      (node (ref "D13") (pin "A") (pinfunction "A_A") (pintype "passive"))
      (node (ref "L1") (pin "1") (pinfunction "1_1") (pintype "passive"))
      (node (ref "L1") (pin "1B") (pinfunction "1_1B") (pintype "passive"))
      (node (ref "U1") (pin "8") (pinfunction "SW_8") (pintype "input"))
    )
    (net (code "65") (name "Net-(U2-IN_P)") (class "Default")
      (node (ref "R14") (pin "2") (pinfunction "2_2") (pintype "passive"))
      (node (ref "R15") (pin "2") (pinfunction "2_2") (pintype "passive"))
      (node (ref "U2") (pin "6") (pinfunction "IN_P_6") (pintype "input"))
    )
    (net (code "66") (name "Net-(U2-OUT_SNK)") (class "Default")
      (node (ref "R17") (pin "1") (pinfunction "1_1") (pintype "passive"))
      (node (ref "U2") (pin "3") (pinfunction "OUT_SNK_3") (pintype "output"))
    )
    (net (code "67") (name "Net-(U2-OUT_SRC)") (class "Default")
      (node (ref "R16") (pin "1") (pinfunction "1_1") (pintype "passive"))
      (node (ref "U2") (pin "2") (pinfunction "OUT_SRC_2") (pintype "output"))
    )
    (net (code "68") (name "Net-(U2-VDD)") (class "Default")
      (node (ref "C35") (pin "2") (pinfunction "2_2") (pintype "passive"))
      (node (ref "C36") (pin "2") (pinfunction "2_2") (pintype "passive"))
      (node (ref "L7") (pin "2") (pinfunction "2_2") (pintype "passive"))
      (node (ref "SJ8") (pin "2") (pinfunction "2_2") (pintype "bidirectional"))
      (node (ref "U2") (pin "1") (pinfunction "VDD_1") (pintype "power_in"))
    )
    (net (code "69") (name "Net-(U3-BOOT0)") (class "Default")
      (node (ref "SJ1") (pin "2") (pinfunction "2_2") (pintype "passive"))
      (node (ref "U3") (pin "1") (pinfunction "BOOT0_1") (pintype "input"))
    )
    (net (code "70") (name "Net-(U3-PB1{slash}TIM1_CH3N{slash}ADC_IN9)") (class "Default")
      (node (ref "R52") (pin "1") (pinfunction "1_1") (pintype "passive"))
      (node (ref "U3") (pin "14") (pinfunction "PB1/TIM1_CH3N/ADC_IN9_14") (pintype "bidirectional"))
    )
    (net (code "71") (name "Net-(U3-PF0{slash}OSC_IN)") (class "Default")
      (node (ref "C56") (pin "1") (pinfunction "1_1") (pintype "passive"))
      (node (ref "U3") (pin "2") (pinfunction "PF0/OSC_IN_2") (pintype "bidirectional"))
      (node (ref "Y1") (pin "3") (pinfunction "2_3") (pintype "passive"))
    )
    (net (code "72") (name "Net-(U3-PF1{slash}OSC_OUT)") (class "Default")
      (node (ref "C55") (pin "1") (pinfunction "1_1") (pintype "passive"))
      (node (ref "U3") (pin "3") (pinfunction "PF1/OSC_OUT_3") (pintype "bidirectional"))
      (node (ref "Y1") (pin "1") (pinfunction "1_1") (pintype "passive"))
    )
    (net (code "73") (name "Net-(U6-CAP)") (class "Default")
      (node (ref "C51") (pin "1") (pinfunction "1_1") (pintype "passive"))
      (node (ref "U6") (pin "11") (pinfunction "CAP_11") (pintype "passive"))
    )
    (net (code "74") (name "Net-(U6-OV)") (class "Default")
      (node (ref "R53") (pin "1") (pinfunction "1_1") (pintype "passive"))
      (node (ref "R54") (pin "1") (pinfunction "1_1") (pintype "passive"))
      (node (ref "R55") (pin "1") (pinfunction "1_1") (pintype "passive"))
      (node (ref "U6") (pin "5") (pinfunction "OV_5") (pintype "passive"))
    )
    (net (code "75") (name "Net-(U6-SW)") (class "Default")
      (node (ref "R53") (pin "2") (pinfunction "2_2") (pintype "passive"))
      (node (ref "U6") (pin "4") (pinfunction "SW_4") (pintype "passive"))
    )
    (net (code "76") (name "Net-(U7-ISEL)") (class "Default")
      (node (ref "JP5") (pin "1") (pinfunction "1_1") (pintype "passive"))
      (node (ref "R46") (pin "1") (pinfunction "1_1") (pintype "passive"))
      (node (ref "U7") (pin "5") (pinfunction "ISEL_5") (pintype "bidirectional"))
    )
    (net (code "77") (name "Net-(U7-V5V)") (class "Default")
      (node (ref "C64") (pin "2") (pinfunction "2_2") (pintype "passive"))
      (node (ref "U7") (pin "13") (pinfunction "V5V_13") (pintype "bidirectional"))
    )
    (net (code "78") (name "Net-(U7-VCC1)") (class "Default")
      (node (ref "Q6") (pin "10") (pinfunction "D_10") (pintype "passive"))
      (node (ref "Q6") (pin "5") (pinfunction "D_5") (pintype "passive"))
      (node (ref "Q6") (pin "6") (pinfunction "D_6") (pintype "passive"))
      (node (ref "Q6") (pin "7") (pinfunction "D_7") (pintype "passive"))
      (node (ref "Q6") (pin "8") (pinfunction "D_8") (pintype "passive"))
      (node (ref "Q6") (pin "9") (pinfunction "D_9") (pintype "passive"))
      (node (ref "U7") (pin "16") (pinfunction "VCC1_16") (pintype "bidirectional"))
    )
    (net (code "79") (name "Net-(U7-VG_A)") (class "Default")
      (node (ref "R30") (pin "2") (pinfunction "2_2") (pintype "passive"))
      (node (ref "U7") (pin "15") (pinfunction "VG_A_15") (pintype "bidirectional"))
    )
    (net (code "80") (name "Net-(U7-VOUT)") (class "Default")
      (node (ref "R31") (pin "2") (pinfunction "2_2") (pintype "passive"))
      (node (ref "U7") (pin "14") (pinfunction "VOUT_14") (pintype "bidirectional"))
    )
    (net (code "81") (name "Net-(U7-VSEL)") (class "Default")
      (node (ref "R47") (pin "1") (pinfunction "1_1") (pintype "passive"))
      (node (ref "R48") (pin "1") (pinfunction "1_1") (pintype "passive"))
      (node (ref "U7") (pin "4") (pinfunction "VSEL_4") (pintype "bidirectional"))
    )
    (net (code "82") (name "Net-(VR1-E)") (class "Default")
      (node (ref "R37") (pin "2") (pinfunction "2_2") (pintype "passive"))
      (node (ref "R4") (pin "1") (pinfunction "1_1") (pintype "passive"))
      (node (ref "VR1") (pin "3") (pinfunction "E_3") (pintype "passive"))
    )
    (net (code "83") (name "Net-(VR4-A)") (class "Default")
      (node (ref "C34") (pin "1") (pinfunction "1_1") (pintype "passive"))
      (node (ref "R10") (pin "2") (pinfunction "2_2") (pintype "passive"))
      (node (ref "R11") (pin "2") (pinfunction "2_2") (pintype "passive"))
      (node (ref "VR4") (pin "1") (pinfunction "A_1") (pintype "passive"))
    )
    (net (code "84") (name "Net-(VR4-E)") (class "Default")
      (node (ref "SJ2") (pin "1") (pinfunction "1_1") (pintype "passive"))
      (node (ref "VR4") (pin "2") (pinfunction "S_2") (pintype "passive"))
      (node (ref "VR4") (pin "3") (pinfunction "E_3") (pintype "passive"))
    )
    (net (code "85") (name "PWR-ATTENU") (class "Default")
      (node (ref "R9") (pin "1") (pinfunction "1_1") (pintype "passive"))
      (node (ref "TP2") (pin "1") (pinfunction "1_1") (pintype "bidirectional"))
      (node (ref "U3") (pin "12") (pinfunction "PA6/TIM3_CH1/TIM16_CH1/ADC_IN6_12") (pintype "bidirectional"))
    )
    (net (code "86") (name "RF-GATE") (class "Default")
      (node (ref "D9") (pin "C") (pinfunction "C_C") (pintype "passive"))
      (node (ref "L8") (pin "2") (pinfunction "2_2") (pintype "passive"))
      (node (ref "Q1") (pin "1") (pinfunction "G_1") (pintype "passive"))
      (node (ref "R12") (pin "2") (pinfunction "2_2") (pintype "passive"))
      (node (ref "R13") (pin "2") (pinfunction "2_2") (pintype "passive"))
      (node (ref "TVS2") (pin "C") (pinfunction "2_C") (pintype "passive"))
    )
    (net (code "87") (name "RF-GEN") (class "Default")
      (node (ref "R14") (pin "1") (pinfunction "1_1") (pintype "passive"))
      (node (ref "R52") (pin "2") (pinfunction "2_2") (pintype "passive"))
      (node (ref "TP1") (pin "1") (pinfunction "1_1") (pintype "bidirectional"))
    )
    (net (code "88") (name "RF-OUT") (class "Default")
      (node (ref "C33") (pin "1") (pinfunction "1_1") (pintype "passive"))
      (node (ref "JP1") (pin "1") (pinfunction "SIGNAL_1") (pintype "passive"))
      (node (ref "R21") (pin "1") (pinfunction "1_1") (pintype "passive"))
      (node (ref "T1") (pin "P2") (pinfunction "P1_P2") (pintype "bidirectional"))
    )
    (net (code "89") (name "SCL") (class "Default")
      (node (ref "R36") (pin "1") (pinfunction "1_1") (pintype "passive"))
      (node (ref "U3") (pin "17") (pinfunction "PA9/USART1_TX/TIM1_CH2/I2C1_SCL_17") (pintype "bidirectional"))
      (node (ref "U4") (pin "3") (pinfunction "SCL_3") (pintype "bidirectional"))
    )
    (net (code "90") (name "SDA") (class "Default")
      (node (ref "R35") (pin "1") (pinfunction "1_1") (pintype "passive"))
      (node (ref "U3") (pin "18") (pinfunction "PA10/USART1_RX/TIM1_CH3/I2C1_SDA_18") (pintype "bidirectional"))
      (node (ref "U4") (pin "4") (pinfunction "SDA_4") (pintype "bidirectional"))
    )
    (net (code "91") (name "SWCLK") (class "Default")
      (node (ref "JP4") (pin "2") (pinfunction "2_2") (pintype "passive"))
      (node (ref "U3") (pin "20") (pinfunction "PA14/USART2_TX/SWCLK_20") (pintype "bidirectional"))
    )
    (net (code "92") (name "SWDIO") (class "Default")
      (node (ref "JP4") (pin "4") (pinfunction "4_4") (pintype "passive"))
      (node (ref "SJ3") (pin "2") (pinfunction "2_2") (pintype "passive"))
      (node (ref "U3") (pin "19") (pinfunction "PA13/IR_OUT/SWDIO_19") (pintype "bidirectional"))
    )
    (net (code "93") (name "THERM-1") (class "Default")
      (node (ref "C59") (pin "1") (pinfunction "1_1") (pintype "passive"))
      (node (ref "R50") (pin "1") (pinfunction "1_1") (pintype "passive"))
      (node (ref "THERM1") (pin "1") (pinfunction "1_1") (pintype "passive"))
      (node (ref "U3") (pin "7") (pinfunction "PA1/ADC_IN1_7") (pintype "bidirectional"))
    )
    (net (code "94") (name "THERM-2") (class "Default")
      (node (ref "C60") (pin "1") (pinfunction "1_1") (pintype "passive"))
      (node (ref "R51") (pin "1") (pinfunction "1_1") (pintype "passive"))
      (node (ref "THERM2") (pin "1") (pinfunction "1_1") (pintype "passive"))
      (node (ref "U3") (pin "8") (pinfunction "PA2/USART1_TX/ADC_IN2_8") (pintype "bidirectional"))
    )
    (net (code "95") (name "TIP-DET") (class "Default")
      (node (ref "C41") (pin "1") (pinfunction "1_1") (pintype "passive"))
      (node (ref "Q3") (pin "3") (pinfunction "C_3") (pintype "passive"))
      (node (ref "R18") (pin "1") (pinfunction "1_1") (pintype "passive"))
      (node (ref "U3") (pin "11") (pinfunction "PA5/ADC_IN5_11") (pintype "bidirectional"))
    )
    (net (code "96") (name "VCD") (class "Default")
      (node (ref "C51") (pin "2") (pinfunction "2_2") (pintype "passive"))
      (node (ref "C52") (pin "1") (pinfunction "1_1") (pintype "passive"))
      (node (ref "Q4") (pin "5") (pinfunction "D_5") (pintype "passive"))
      (node (ref "Q4") (pin "6") (pinfunction "D_6") (pintype "passive"))
      (node (ref "Q4") (pin "7") (pinfunction "D_7") (pintype "passive"))
      (node (ref "Q4") (pin "8") (pinfunction "D_8") (pintype "passive"))
      (node (ref "Q4") (pin "9") (pinfunction "D_9") (pintype "passive"))
      (node (ref "Q5") (pin "5") (pinfunction "D_5") (pintype "passive"))
      (node (ref "Q5") (pin "6") (pinfunction "D_6") (pintype "passive"))
      (node (ref "Q5") (pin "7") (pinfunction "D_7") (pintype "passive"))
      (node (ref "Q5") (pin "8") (pinfunction "D_8") (pintype "passive"))
      (node (ref "Q5") (pin "9") (pinfunction "D_9") (pintype "passive"))
      (node (ref "R34") (pin "2") (pinfunction "2_2") (pintype "passive"))
      (node (ref "U6") (pin "10") (pinfunction "VS_10") (pintype "power_in"))
      (node (ref "U6") (pin "12") (pinfunction "C_12") (pintype "passive"))
    )
    (net (code "97") (name "unconnected-(FAN1-PadT)") (class "Default")
      (node (ref "FAN1") (pin "T") (pinfunction "T_T") (pintype "bidirectional"))
    )
    (net (code "98") (name "unconnected-(JP4-Pad6)") (class "Default")
      (node (ref "JP4") (pin "6") (pinfunction "6_6") (pintype "passive"))
    )
    (net (code "99") (name "unconnected-(U1-EN-Pad3)") (class "Default")
      (node (ref "U1") (pin "3") (pinfunction "EN_3") (pintype "input"))
    )
    (net (code "100") (name "unconnected-(U6-RTN-Pad13)") (class "Default")
      (node (ref "U6") (pin "13") (pinfunction "RTN_13") (pintype "passive"))
    )
    (net (code "101") (name "unconnected-(U7-DN-Pad10)") (class "Default")
      (node (ref "U7") (pin "10") (pinfunction "DN_10") (pintype "bidirectional"))
    )
    (net (code "102") (name "unconnected-(U7-DP-Pad9)") (class "Default")
      (node (ref "U7") (pin "9") (pinfunction "DP_9") (pintype "bidirectional"))
    )
    (net (code "103") (name "unconnected-(U7-GPIO-Pad6)") (class "Default")
      (node (ref "U7") (pin "6") (pinfunction "GPIO_6") (pintype "bidirectional"))
    )
    (net (code "104") (name "unconnected-(U7-VFB-Pad7)") (class "Default")
      (node (ref "U7") (pin "7") (pinfunction "VFB_7") (pintype "bidirectional"))
    )
  )
)
